# Monitoring_CB.net
KiCad netlist of a schematic drawn in Altium Designer
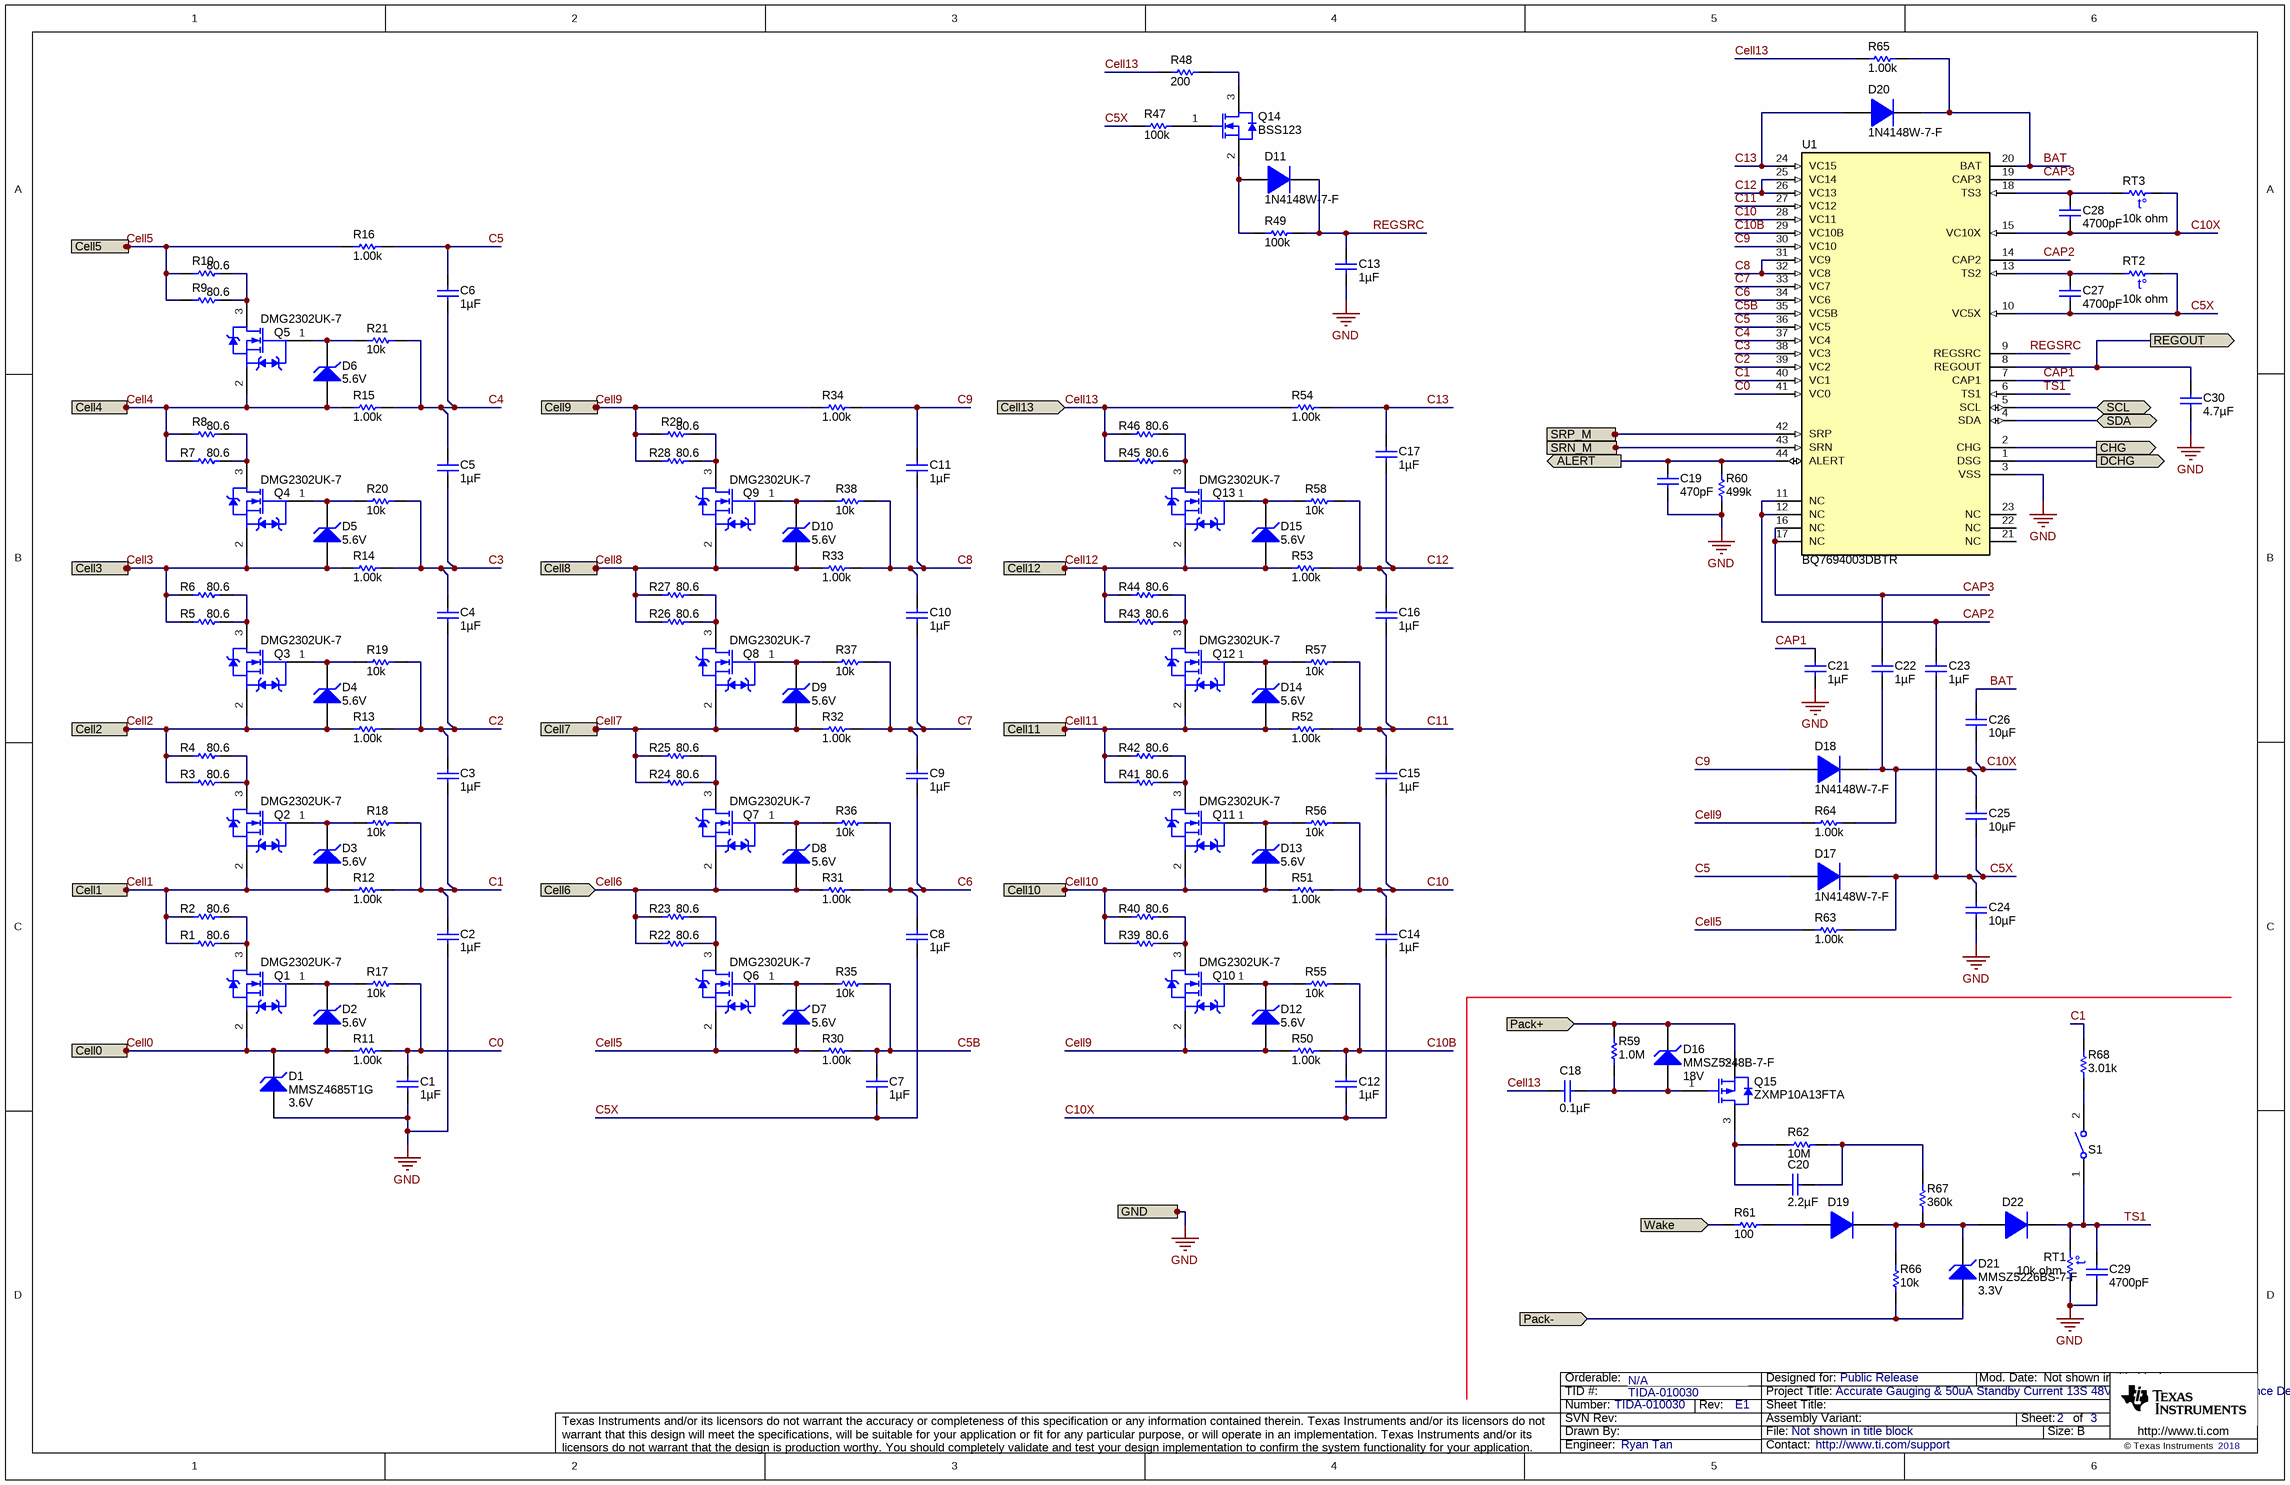
[diagram p0: Monitoring & CB.SchDoc]

(export (version "E")
  (design (tool "Eeschema 10.0.6"))
  (components
    (comp (ref "C1")
      (value "GRM188R71C105KE15D")
      (footprint "0603")
      (description "CAP, CERM, 1 µF, 16 V,+/- 10%, X7R, 0603")
      (fields
        (field (name "VALUEDISPLAYED") "1µF")
        (field (name "MANUFACTURER") "MuRata")
        (field (name "PUBLISHER") "Texas Instruments")
      )
      (libsource (lib "Capacitor_Ceramic") (part "GRM188R71C105KE15D"))
    )
    (comp (ref "C2")
      (value "GRM188R71C105KE15D")
      (footprint "0603S")
      (description "CAP, CERM, 1 µF, 16 V,+/- 10%, X7R, 0603")
      (fields
        (field (name "VALUEDISPLAYED") "1µF")
        (field (name "MANUFACTURER") "MuRata")
        (field (name "PUBLISHER") "Texas Instruments")
      )
      (libsource (lib "Capacitor_Ceramic") (part "GRM188R71C105KE15D"))
    )
    (comp (ref "C3")
      (value "GRM188R71C105KE15D")
      (footprint "0603")
      (description "CAP, CERM, 1 µF, 16 V,+/- 10%, X7R, 0603")
      (fields
        (field (name "VALUEDISPLAYED") "1µF")
        (field (name "MANUFACTURER") "MuRata")
        (field (name "PUBLISHER") "Texas Instruments")
      )
      (libsource (lib "Capacitor_Ceramic") (part "GRM188R71C105KE15D"))
    )
    (comp (ref "C4")
      (value "GRM188R71C105KE15D")
      (footprint "0603")
      (description "CAP, CERM, 1 µF, 16 V,+/- 10%, X7R, 0603")
      (fields
        (field (name "VALUEDISPLAYED") "1µF")
        (field (name "MANUFACTURER") "MuRata")
        (field (name "PUBLISHER") "Texas Instruments")
      )
      (libsource (lib "Capacitor_Ceramic") (part "GRM188R71C105KE15D"))
    )
    (comp (ref "C5")
      (value "GRM188R71C105KE15D")
      (footprint "0603")
      (description "CAP, CERM, 1 µF, 16 V,+/- 10%, X7R, 0603")
      (fields
        (field (name "VALUEDISPLAYED") "1µF")
        (field (name "MANUFACTURER") "MuRata")
        (field (name "PUBLISHER") "Texas Instruments")
      )
      (libsource (lib "Capacitor_Ceramic") (part "GRM188R71C105KE15D"))
    )
    (comp (ref "C6")
      (value "GRM188R71C105KE15D")
      (footprint "0603")
      (description "CAP, CERM, 1 µF, 16 V,+/- 10%, X7R, 0603")
      (fields
        (field (name "VALUEDISPLAYED") "1µF")
        (field (name "MANUFACTURER") "MuRata")
        (field (name "PUBLISHER") "Texas Instruments")
      )
      (libsource (lib "Capacitor_Ceramic") (part "GRM188R71C105KE15D"))
    )
    (comp (ref "C7")
      (value "GRM188R71C105KE15D")
      (footprint "0603S")
      (description "CAP, CERM, 1 µF, 16 V,+/- 10%, X7R, 0603")
      (fields
        (field (name "VALUEDISPLAYED") "1µF")
        (field (name "MANUFACTURER") "MuRata")
        (field (name "PUBLISHER") "Texas Instruments")
      )
      (libsource (lib "Capacitor_Ceramic") (part "GRM188R71C105KE15D"))
    )
    (comp (ref "C8")
      (value "GRM188R71C105KE15D")
      (footprint "0603S")
      (description "CAP, CERM, 1 µF, 16 V,+/- 10%, X7R, 0603")
      (fields
        (field (name "VALUEDISPLAYED") "1µF")
        (field (name "MANUFACTURER") "MuRata")
        (field (name "PUBLISHER") "Texas Instruments")
      )
      (libsource (lib "Capacitor_Ceramic") (part "GRM188R71C105KE15D"))
    )
    (comp (ref "C9")
      (value "GRM188R71C105KE15D")
      (footprint "0603")
      (description "CAP, CERM, 1 µF, 16 V,+/- 10%, X7R, 0603")
      (fields
        (field (name "VALUEDISPLAYED") "1µF")
        (field (name "MANUFACTURER") "MuRata")
        (field (name "PUBLISHER") "Texas Instruments")
      )
      (libsource (lib "Capacitor_Ceramic") (part "GRM188R71C105KE15D"))
    )
    (comp (ref "C10")
      (value "GRM188R71C105KE15D")
      (footprint "0603")
      (description "CAP, CERM, 1 µF, 16 V,+/- 10%, X7R, 0603")
      (fields
        (field (name "VALUEDISPLAYED") "1µF")
        (field (name "MANUFACTURER") "MuRata")
        (field (name "PUBLISHER") "Texas Instruments")
      )
      (libsource (lib "Capacitor_Ceramic") (part "GRM188R71C105KE15D"))
    )
    (comp (ref "C11")
      (value "GRM188R71C105KE15D")
      (footprint "0603")
      (description "CAP, CERM, 1 µF, 16 V,+/- 10%, X7R, 0603")
      (fields
        (field (name "VALUEDISPLAYED") "1µF")
        (field (name "MANUFACTURER") "MuRata")
        (field (name "PUBLISHER") "Texas Instruments")
      )
      (libsource (lib "Capacitor_Ceramic") (part "GRM188R71C105KE15D"))
    )
    (comp (ref "C12")
      (value "GRM188R71C105KE15D")
      (footprint "0603")
      (description "CAP, CERM, 1 µF, 16 V,+/- 10%, X7R, 0603")
      (fields
        (field (name "VALUEDISPLAYED") "1µF")
        (field (name "MANUFACTURER") "MuRata")
        (field (name "PUBLISHER") "Texas Instruments")
      )
      (libsource (lib "Capacitor_Ceramic") (part "GRM188R71C105KE15D"))
    )
    (comp (ref "C13")
      (value "C1608X7R1V105K080AC")
      (footprint "0603S")
      (description "CAP, CERM, 1 µF, 35 V,+/- 10%, X7R, 0603")
      (fields
        (field (name "VALUEDISPLAYED") "1µF")
        (field (name "MANUFACTURER") "TDK")
        (field (name "PUBLISHER") "Texas Instruments")
      )
      (libsource (lib "Capacitor_Ceramic") (part "C1608X7R1V105K080AC"))
    )
    (comp (ref "C14")
      (value "GRM188R71C105KE15D")
      (footprint "0603")
      (description "CAP, CERM, 1 µF, 16 V,+/- 10%, X7R, 0603")
      (fields
        (field (name "VALUEDISPLAYED") "1µF")
        (field (name "MANUFACTURER") "MuRata")
        (field (name "PUBLISHER") "Texas Instruments")
      )
      (libsource (lib "Capacitor_Ceramic") (part "GRM188R71C105KE15D"))
    )
    (comp (ref "C15")
      (value "GRM188R71C105KE15D")
      (footprint "0603")
      (description "CAP, CERM, 1 µF, 16 V,+/- 10%, X7R, 0603")
      (fields
        (field (name "VALUEDISPLAYED") "1µF")
        (field (name "MANUFACTURER") "MuRata")
        (field (name "PUBLISHER") "Texas Instruments")
      )
      (libsource (lib "Capacitor_Ceramic") (part "GRM188R71C105KE15D"))
    )
    (comp (ref "C16")
      (value "GRM188R71C105KE15D")
      (footprint "0603")
      (description "CAP, CERM, 1 µF, 16 V,+/- 10%, X7R, 0603")
      (fields
        (field (name "VALUEDISPLAYED") "1µF")
        (field (name "MANUFACTURER") "MuRata")
        (field (name "PUBLISHER") "Texas Instruments")
      )
      (libsource (lib "Capacitor_Ceramic") (part "GRM188R71C105KE15D"))
    )
    (comp (ref "C17")
      (value "GRM188R71C105KE15D")
      (footprint "0603")
      (description "CAP, CERM, 1 µF, 16 V,+/- 10%, X7R, 0603")
      (fields
        (field (name "VALUEDISPLAYED") "1µF")
        (field (name "MANUFACTURER") "MuRata")
        (field (name "PUBLISHER") "Texas Instruments")
      )
      (libsource (lib "Capacitor_Ceramic") (part "GRM188R71C105KE15D"))
    )
    (comp (ref "C18")
      (value "CGA4J2X7R2A104K125AA")
      (footprint "0805_HV")
      (description "CAP, CERM, 0.1 µF, 100 V,+/- 10%, X7R, AEC-Q200 Grade 1, 0805")
      (fields
        (field (name "VALUEDISPLAYED") "0.1µF")
        (field (name "MANUFACTURER") "TDK")
        (field (name "PUBLISHER") "Texas Instruments")
      )
      (libsource (lib "Capacitor_Ceramic") (part "CGA4J2X7R2A104K125AA"))
    )
    (comp (ref "C19")
      (value "GCM1885C1H471JA16D")
      (footprint "0603")
      (description "CAP, CERM, 470 pF, 50 V,+/- 5%, C0G/NP0, AEC-Q200 Grade 1, 0603")
      (fields
        (field (name "VALUEDISPLAYED") "470pF")
        (field (name "MANUFACTURER") "MuRata")
        (field (name "PUBLISHER") "Texas Instruments")
      )
      (libsource (lib "Capacitor_Ceramic") (part "GCM1885C1H471JA16D"))
    )
    (comp (ref "C20")
      (value "GRM32ER72A225KA35L")
      (footprint "1210_270")
      (description "CAP, CERM, 2.2 µF, 100 V,+/- 10%, X7R, 1210")
      (fields
        (field (name "VALUEDISPLAYED") "2.2µF")
        (field (name "MANUFACTURER") "MuRata")
        (field (name "PUBLISHER") "Texas Instruments")
      )
      (libsource (lib "Capacitor_Ceramic") (part "GRM32ER72A225KA35L"))
    )
    (comp (ref "C21")
      (value "GRM188R71C105KE15D")
      (footprint "0603S")
      (description "CAP, CERM, 1 µF, 16 V,+/- 10%, X7R, 0603")
      (fields
        (field (name "VALUEDISPLAYED") "1µF")
        (field (name "MANUFACTURER") "MuRata")
        (field (name "PUBLISHER") "Texas Instruments")
      )
      (libsource (lib "Capacitor_Ceramic") (part "GRM188R71C105KE15D"))
    )
    (comp (ref "C22")
      (value "GRM188R71C105KE15D")
      (footprint "0603S")
      (description "CAP, CERM, 1 µF, 16 V,+/- 10%, X7R, 0603")
      (fields
        (field (name "VALUEDISPLAYED") "1µF")
        (field (name "MANUFACTURER") "MuRata")
        (field (name "PUBLISHER") "Texas Instruments")
      )
      (libsource (lib "Capacitor_Ceramic") (part "GRM188R71C105KE15D"))
    )
    (comp (ref "C23")
      (value "GRM188R71C105KE15D")
      (footprint "0603S")
      (description "CAP, CERM, 1 µF, 16 V,+/- 10%, X7R, 0603")
      (fields
        (field (name "VALUEDISPLAYED") "1µF")
        (field (name "MANUFACTURER") "MuRata")
        (field (name "PUBLISHER") "Texas Instruments")
      )
      (libsource (lib "Capacitor_Ceramic") (part "GRM188R71C105KE15D"))
    )
    (comp (ref "C24")
      (value "C3225X5R1H106K250AB")
      (footprint "1210_280")
      (description "CAP, CERM, 10 µF, 50 V,+/- 10%, X5R, 1210")
      (fields
        (field (name "VALUEDISPLAYED") "10µF")
        (field (name "MANUFACTURER") "TDK")
        (field (name "PUBLISHER") "Texas Instruments")
      )
      (libsource (lib "Capacitor_Ceramic") (part "C3225X5R1H106K250AB"))
    )
    (comp (ref "C25")
      (value "C3225X5R1H106K250AB")
      (footprint "1210_280")
      (description "CAP, CERM, 10 µF, 50 V,+/- 10%, X5R, 1210")
      (fields
        (field (name "VALUEDISPLAYED") "10µF")
        (field (name "MANUFACTURER") "TDK")
        (field (name "PUBLISHER") "Texas Instruments")
      )
      (libsource (lib "Capacitor_Ceramic") (part "C3225X5R1H106K250AB"))
    )
    (comp (ref "C26")
      (value "C3225X5R1H106K250AB")
      (footprint "1210_280")
      (description "CAP, CERM, 10 µF, 50 V,+/- 10%, X5R, 1210")
      (fields
        (field (name "VALUEDISPLAYED") "10µF")
        (field (name "MANUFACTURER") "TDK")
        (field (name "PUBLISHER") "Texas Instruments")
      )
      (libsource (lib "Capacitor_Ceramic") (part "C3225X5R1H106K250AB"))
    )
    (comp (ref "C27")
      (value "GCM188R71H472KA37D")
      (footprint "0603S")
      (description "CAP, CERM, 4700 pF, 50 V,+/- 10%, X7R, AEC-Q200 Grade 1, 0603")
      (fields
        (field (name "VALUEDISPLAYED") "4700pF")
        (field (name "MANUFACTURER") "MuRata")
        (field (name "PUBLISHER") "Texas Instruments")
      )
      (libsource (lib "Capacitor_Ceramic") (part "GCM188R71H472KA37D"))
    )
    (comp (ref "C28")
      (value "GCM188R71H472KA37D")
      (footprint "0603")
      (description "CAP, CERM, 4700 pF, 50 V,+/- 10%, X7R, AEC-Q200 Grade 1, 0603")
      (fields
        (field (name "VALUEDISPLAYED") "4700pF")
        (field (name "MANUFACTURER") "MuRata")
        (field (name "PUBLISHER") "Texas Instruments")
      )
      (libsource (lib "Capacitor_Ceramic") (part "GCM188R71H472KA37D"))
    )
    (comp (ref "C29")
      (value "GCM188R71H472KA37D")
      (footprint "0603")
      (description "CAP, CERM, 4700 pF, 50 V,+/- 10%, X7R, AEC-Q200 Grade 1, 0603")
      (fields
        (field (name "VALUEDISPLAYED") "4700pF")
        (field (name "MANUFACTURER") "MuRata")
        (field (name "PUBLISHER") "Texas Instruments")
      )
      (libsource (lib "Capacitor_Ceramic") (part "GCM188R71H472KA37D"))
    )
    (comp (ref "C30")
      (value "GRM188R61C475KAAJ")
      (footprint "0603S")
      (description "CAP, CERM, 4.7 µF, 16 V,+/- 10%, X5R, 0603")
      (fields
        (field (name "VALUEDISPLAYED") "4.7µF")
        (field (name "MANUFACTURER") "MuRata")
        (field (name "PUBLISHER") "Texas Instruments")
      )
      (libsource (lib "Capacitor_Ceramic") (part "GRM188R61C475KAAJ"))
    )
    (comp (ref "D1")
      (value "MMSZ4685T1G")
      (footprint "SOD-123")
      (description "Diode, Zener, 3.6 V, 500 mW, SOD-123")
      (fields
        (field (name "ALTIUM_VALUE") "3.6V")
        (field (name "MANUFACTURER") "ON Semiconductor")
        (field (name "SYMBOLCREATOR") "a0412235")
        (field (name "PUBLISHER") "Texas Instruments")
      )
      (libsource (lib "ZenerDiodes") (part "MMSZ4685T1G"))
    )
    (comp (ref "D2")
      (value "5.6V")
      (footprint "SOD-523")
      (description "Diode, Zener, 5.6 V, 300 mW, SOD-523")
      (fields
        (field (name "PARTNUMBER") "BZT52C5V6T-7")
        (field (name "MANUFACTURER") "Diodes Inc.")
        (field (name "SYMBOLCREATOR") "a0412235")
        (field (name "PUBLISHER") "Texas Instruments")
      )
      (libsource (lib "ZenerDiodes") (part "BZT52C5V6T-7"))
    )
    (comp (ref "D3")
      (value "5.6V")
      (footprint "SOD-523")
      (description "Diode, Zener, 5.6 V, 300 mW, SOD-523")
      (fields
        (field (name "PARTNUMBER") "BZT52C5V6T-7")
        (field (name "MANUFACTURER") "Diodes Inc.")
        (field (name "SYMBOLCREATOR") "a0412235")
        (field (name "PUBLISHER") "Texas Instruments")
      )
      (libsource (lib "ZenerDiodes") (part "BZT52C5V6T-7"))
    )
    (comp (ref "D4")
      (value "5.6V")
      (footprint "SOD-523")
      (description "Diode, Zener, 5.6 V, 300 mW, SOD-523")
      (fields
        (field (name "PARTNUMBER") "BZT52C5V6T-7")
        (field (name "MANUFACTURER") "Diodes Inc.")
        (field (name "SYMBOLCREATOR") "a0412235")
        (field (name "PUBLISHER") "Texas Instruments")
      )
      (libsource (lib "ZenerDiodes") (part "BZT52C5V6T-7"))
    )
    (comp (ref "D5")
      (value "5.6V")
      (footprint "SOD-523")
      (description "Diode, Zener, 5.6 V, 300 mW, SOD-523")
      (fields
        (field (name "PARTNUMBER") "BZT52C5V6T-7")
        (field (name "MANUFACTURER") "Diodes Inc.")
        (field (name "SYMBOLCREATOR") "a0412235")
        (field (name "PUBLISHER") "Texas Instruments")
      )
      (libsource (lib "ZenerDiodes") (part "BZT52C5V6T-7"))
    )
    (comp (ref "D6")
      (value "5.6V")
      (footprint "SOD-523")
      (description "Diode, Zener, 5.6 V, 300 mW, SOD-523")
      (fields
        (field (name "PARTNUMBER") "BZT52C5V6T-7")
        (field (name "MANUFACTURER") "Diodes Inc.")
        (field (name "SYMBOLCREATOR") "a0412235")
        (field (name "PUBLISHER") "Texas Instruments")
      )
      (libsource (lib "ZenerDiodes") (part "BZT52C5V6T-7"))
    )
    (comp (ref "D7")
      (value "5.6V")
      (footprint "SOD-523")
      (description "Diode, Zener, 5.6 V, 300 mW, SOD-523")
      (fields
        (field (name "PARTNUMBER") "BZT52C5V6T-7")
        (field (name "MANUFACTURER") "Diodes Inc.")
        (field (name "SYMBOLCREATOR") "a0412235")
        (field (name "PUBLISHER") "Texas Instruments")
      )
      (libsource (lib "ZenerDiodes") (part "BZT52C5V6T-7"))
    )
    (comp (ref "D8")
      (value "5.6V")
      (footprint "SOD-523")
      (description "Diode, Zener, 5.6 V, 300 mW, SOD-523")
      (fields
        (field (name "PARTNUMBER") "BZT52C5V6T-7")
        (field (name "MANUFACTURER") "Diodes Inc.")
        (field (name "SYMBOLCREATOR") "a0412235")
        (field (name "PUBLISHER") "Texas Instruments")
      )
      (libsource (lib "ZenerDiodes") (part "BZT52C5V6T-7"))
    )
    (comp (ref "D9")
      (value "5.6V")
      (footprint "SOD-523")
      (description "Diode, Zener, 5.6 V, 300 mW, SOD-523")
      (fields
        (field (name "PARTNUMBER") "BZT52C5V6T-7")
        (field (name "MANUFACTURER") "Diodes Inc.")
        (field (name "SYMBOLCREATOR") "a0412235")
        (field (name "PUBLISHER") "Texas Instruments")
      )
      (libsource (lib "ZenerDiodes") (part "BZT52C5V6T-7"))
    )
    (comp (ref "D10")
      (value "5.6V")
      (footprint "SOD-523")
      (description "Diode, Zener, 5.6 V, 300 mW, SOD-523")
      (fields
        (field (name "PARTNUMBER") "BZT52C5V6T-7")
        (field (name "MANUFACTURER") "Diodes Inc.")
        (field (name "SYMBOLCREATOR") "a0412235")
        (field (name "PUBLISHER") "Texas Instruments")
      )
      (libsource (lib "ZenerDiodes") (part "BZT52C5V6T-7"))
    )
    (comp (ref "D11")
      (value "1N4148W-7-F")
      (footprint "SOD-123")
      (description "Diode, Ultrafast, 100 V, 0.15 A, SOD-123")
      (fields (field (name "MANUFACTURER") "Diodes Inc.") (field (name "PUBLISHER") "Texas Instruments"))
      (libsource (lib "Diode") (part "1N4148W-7-F"))
    )
    (comp (ref "D12")
      (value "5.6V")
      (footprint "SOD-523")
      (description "Diode, Zener, 5.6 V, 300 mW, SOD-523")
      (fields
        (field (name "PARTNUMBER") "BZT52C5V6T-7")
        (field (name "MANUFACTURER") "Diodes Inc.")
        (field (name "SYMBOLCREATOR") "a0412235")
        (field (name "PUBLISHER") "Texas Instruments")
      )
      (libsource (lib "ZenerDiodes") (part "BZT52C5V6T-7"))
    )
    (comp (ref "D13")
      (value "5.6V")
      (footprint "SOD-523")
      (description "Diode, Zener, 5.6 V, 300 mW, SOD-523")
      (fields
        (field (name "PARTNUMBER") "BZT52C5V6T-7")
        (field (name "MANUFACTURER") "Diodes Inc.")
        (field (name "SYMBOLCREATOR") "a0412235")
        (field (name "PUBLISHER") "Texas Instruments")
      )
      (libsource (lib "ZenerDiodes") (part "BZT52C5V6T-7"))
    )
    (comp (ref "D14")
      (value "5.6V")
      (footprint "SOD-523")
      (description "Diode, Zener, 5.6 V, 300 mW, SOD-523")
      (fields
        (field (name "PARTNUMBER") "BZT52C5V6T-7")
        (field (name "MANUFACTURER") "Diodes Inc.")
        (field (name "SYMBOLCREATOR") "a0412235")
        (field (name "PUBLISHER") "Texas Instruments")
      )
      (libsource (lib "ZenerDiodes") (part "BZT52C5V6T-7"))
    )
    (comp (ref "D15")
      (value "5.6V")
      (footprint "SOD-523")
      (description "Diode, Zener, 5.6 V, 300 mW, SOD-523")
      (fields
        (field (name "PARTNUMBER") "BZT52C5V6T-7")
        (field (name "MANUFACTURER") "Diodes Inc.")
        (field (name "SYMBOLCREATOR") "a0412235")
        (field (name "PUBLISHER") "Texas Instruments")
      )
      (libsource (lib "ZenerDiodes") (part "BZT52C5V6T-7"))
    )
    (comp (ref "D16")
      (value "MMSZ5248B-7-F")
      (footprint "SOD-123")
      (description "Diode, Zener, 18 V, 500 mW, SOD-123")
      (fields
        (field (name "ALTIUM_VALUE") "18V")
        (field (name "MANUFACTURER") "Diodes Inc.")
        (field (name "SYMBOLCREATOR") "a0412235")
        (field (name "PUBLISHER") "Texas Instruments")
      )
      (libsource (lib "ZenerDiodes") (part "MMSZ5248B-7-F"))
    )
    (comp (ref "D17")
      (value "1N4148W-7-F")
      (footprint "SOD-123")
      (description "Diode, Ultrafast, 100 V, 0.15 A, SOD-123")
      (fields (field (name "MANUFACTURER") "Diodes Inc.") (field (name "PUBLISHER") "Texas Instruments"))
      (libsource (lib "Diode") (part "1N4148W-7-F"))
    )
    (comp (ref "D18")
      (value "1N4148W-7-F")
      (footprint "SOD-123")
      (description "Diode, Ultrafast, 100 V, 0.15 A, SOD-123")
      (fields (field (name "MANUFACTURER") "Diodes Inc.") (field (name "PUBLISHER") "Texas Instruments"))
      (libsource (lib "Diode") (part "1N4148W-7-F"))
    )
    (comp (ref "D19")
      (value "SBR0220T5-7")
      (footprint "SOD-523")
      (description "Diode, Super Barrier Rectifier, 20 V, 0.2 A, SOD-523")
      (fields (field (name "MANUFACTURER") "Diodes Inc.") (field (name "PUBLISHER") "Texas Instruments"))
      (libsource (lib "Diode") (part "SBR0220T5-7"))
    )
    (comp (ref "D20")
      (value "1N4148W-7-F")
      (footprint "SOD-123")
      (description "Diode, Ultrafast, 100 V, 0.15 A, SOD-123")
      (fields (field (name "MANUFACTURER") "Diodes Inc.") (field (name "PUBLISHER") "Texas Instruments"))
      (libsource (lib "Diode") (part "1N4148W-7-F"))
    )
    (comp (ref "D21")
      (value "MMSZ5226BS-7-F")
      (footprint "SOD-323")
      (description "Diode, Zener, 3.3 V, 200 mW, SOD-323")
      (fields
        (field (name "ALTIUM_VALUE") "3.3V")
        (field (name "MANUFACTURER") "Diodes Inc.")
        (field (name "SYMBOLCREATOR") "a0412235")
        (field (name "PUBLISHER") "Texas Instruments")
      )
      (libsource (lib "ZenerDiodes") (part "MMSZ5226BS-7-F"))
    )
    (comp (ref "D22")
      (value "SBR0220T5-7")
      (footprint "SOD-523")
      (description "Diode, Super Barrier Rectifier, 20 V, 0.2 A, SOD-523")
      (fields (field (name "MANUFACTURER") "Diodes Inc.") (field (name "PUBLISHER") "Texas Instruments"))
      (libsource (lib "Diode") (part "SBR0220T5-7"))
    )
    (comp (ref "Q1")
      (value "DMG2302UK-7")
      (footprint "SOT-23")
      (description "MOSFET, N-CH, 20 V, 2.8 A, AEC-Q101, SOT-23")
      (fields
        (field (name "MANUFACTURER") "Diodes Inc.")
        (field (name "SYMBOLCREATOR") "x0208325")
        (field (name "PUBLISHER") "Texas Instruments")
      )
      (libsource (lib "FETs") (part "DMG2302UK-7"))
    )
    (comp (ref "Q2")
      (value "DMG2302UK-7")
      (footprint "SOT-23")
      (description "MOSFET, N-CH, 20 V, 2.8 A, AEC-Q101, SOT-23")
      (fields
        (field (name "MANUFACTURER") "Diodes Inc.")
        (field (name "SYMBOLCREATOR") "x0208325")
        (field (name "PUBLISHER") "Texas Instruments")
      )
      (libsource (lib "FETs") (part "DMG2302UK-7"))
    )
    (comp (ref "Q3")
      (value "DMG2302UK-7")
      (footprint "SOT-23")
      (description "MOSFET, N-CH, 20 V, 2.8 A, AEC-Q101, SOT-23")
      (fields
        (field (name "MANUFACTURER") "Diodes Inc.")
        (field (name "SYMBOLCREATOR") "x0208325")
        (field (name "PUBLISHER") "Texas Instruments")
      )
      (libsource (lib "FETs") (part "DMG2302UK-7"))
    )
    (comp (ref "Q4")
      (value "DMG2302UK-7")
      (footprint "SOT-23")
      (description "MOSFET, N-CH, 20 V, 2.8 A, AEC-Q101, SOT-23")
      (fields
        (field (name "MANUFACTURER") "Diodes Inc.")
        (field (name "SYMBOLCREATOR") "x0208325")
        (field (name "PUBLISHER") "Texas Instruments")
      )
      (libsource (lib "FETs") (part "DMG2302UK-7"))
    )
    (comp (ref "Q5")
      (value "DMG2302UK-7")
      (footprint "SOT-23")
      (description "MOSFET, N-CH, 20 V, 2.8 A, AEC-Q101, SOT-23")
      (fields
        (field (name "MANUFACTURER") "Diodes Inc.")
        (field (name "SYMBOLCREATOR") "x0208325")
        (field (name "PUBLISHER") "Texas Instruments")
      )
      (libsource (lib "FETs") (part "DMG2302UK-7"))
    )
    (comp (ref "Q6")
      (value "DMG2302UK-7")
      (footprint "SOT-23")
      (description "MOSFET, N-CH, 20 V, 2.8 A, AEC-Q101, SOT-23")
      (fields
        (field (name "MANUFACTURER") "Diodes Inc.")
        (field (name "SYMBOLCREATOR") "x0208325")
        (field (name "PUBLISHER") "Texas Instruments")
      )
      (libsource (lib "FETs") (part "DMG2302UK-7"))
    )
    (comp (ref "Q7")
      (value "DMG2302UK-7")
      (footprint "SOT-23")
      (description "MOSFET, N-CH, 20 V, 2.8 A, AEC-Q101, SOT-23")
      (fields
        (field (name "MANUFACTURER") "Diodes Inc.")
        (field (name "SYMBOLCREATOR") "x0208325")
        (field (name "PUBLISHER") "Texas Instruments")
      )
      (libsource (lib "FETs") (part "DMG2302UK-7"))
    )
    (comp (ref "Q8")
      (value "DMG2302UK-7")
      (footprint "SOT-23")
      (description "MOSFET, N-CH, 20 V, 2.8 A, AEC-Q101, SOT-23")
      (fields
        (field (name "MANUFACTURER") "Diodes Inc.")
        (field (name "SYMBOLCREATOR") "x0208325")
        (field (name "PUBLISHER") "Texas Instruments")
      )
      (libsource (lib "FETs") (part "DMG2302UK-7"))
    )
    (comp (ref "Q9")
      (value "DMG2302UK-7")
      (footprint "SOT-23")
      (description "MOSFET, N-CH, 20 V, 2.8 A, AEC-Q101, SOT-23")
      (fields
        (field (name "MANUFACTURER") "Diodes Inc.")
        (field (name "SYMBOLCREATOR") "x0208325")
        (field (name "PUBLISHER") "Texas Instruments")
      )
      (libsource (lib "FETs") (part "DMG2302UK-7"))
    )
    (comp (ref "Q10")
      (value "DMG2302UK-7")
      (footprint "SOT-23")
      (description "MOSFET, N-CH, 20 V, 2.8 A, AEC-Q101, SOT-23")
      (fields
        (field (name "MANUFACTURER") "Diodes Inc.")
        (field (name "SYMBOLCREATOR") "x0208325")
        (field (name "PUBLISHER") "Texas Instruments")
      )
      (libsource (lib "FETs") (part "DMG2302UK-7"))
    )
    (comp (ref "Q11")
      (value "DMG2302UK-7")
      (footprint "SOT-23")
      (description "MOSFET, N-CH, 20 V, 2.8 A, AEC-Q101, SOT-23")
      (fields
        (field (name "MANUFACTURER") "Diodes Inc.")
        (field (name "SYMBOLCREATOR") "x0208325")
        (field (name "PUBLISHER") "Texas Instruments")
      )
      (libsource (lib "FETs") (part "DMG2302UK-7"))
    )
    (comp (ref "Q12")
      (value "DMG2302UK-7")
      (footprint "SOT-23")
      (description "MOSFET, N-CH, 20 V, 2.8 A, AEC-Q101, SOT-23")
      (fields
        (field (name "MANUFACTURER") "Diodes Inc.")
        (field (name "SYMBOLCREATOR") "x0208325")
        (field (name "PUBLISHER") "Texas Instruments")
      )
      (libsource (lib "FETs") (part "DMG2302UK-7"))
    )
    (comp (ref "Q13")
      (value "DMG2302UK-7")
      (footprint "SOT-23")
      (description "MOSFET, N-CH, 20 V, 2.8 A, AEC-Q101, SOT-23")
      (fields
        (field (name "MANUFACTURER") "Diodes Inc.")
        (field (name "SYMBOLCREATOR") "x0208325")
        (field (name "PUBLISHER") "Texas Instruments")
      )
      (libsource (lib "FETs") (part "DMG2302UK-7"))
    )
    (comp (ref "Q14")
      (value "BSS123")
      (footprint "SOT-23")
      (description "MOSFET, N-CH, 100 V, 0.17 A, SOT-23")
      (fields
        (field (name "MANUFACTURER") "Fairchild Semiconductor")
        (field (name "PUBLISHER") "Texas Instruments")
      )
      (libsource (lib "FETs") (part "BSS123"))
    )
    (comp (ref "Q15")
      (value "ZXMP10A13FTA")
      (footprint "SOT-23")
      (description "MOSFET, P-CH, -100 V, -0.6 A, SOT-23")
      (fields (field (name "MANUFACTURER") "Diodes Inc.") (field (name "PUBLISHER") "Texas Instruments"))
      (libsource (lib "FETs") (part "ZXMP10A13FTA"))
    )
    (comp (ref "R1")
      (value "CRCW120680R6FKEA")
      (footprint "1206")
      (description "RES, 80.6, 1%, 0.25 W, 1206")
      (fields
        (field (name "VALUEDISPLAYED") "80.6")
        (field (name "MANUFACTURER") "Vishay-Dale")
        (field (name "PUBLISHER") "Texas Instruments")
      )
      (libsource (lib "Resistor_1206") (part "CRCW120680R6FKEA"))
    )
    (comp (ref "R2")
      (value "CRCW120680R6FKEA")
      (footprint "1206")
      (description "RES, 80.6, 1%, 0.25 W, 1206")
      (fields
        (field (name "VALUEDISPLAYED") "80.6")
        (field (name "MANUFACTURER") "Vishay-Dale")
        (field (name "PUBLISHER") "Texas Instruments")
      )
      (libsource (lib "Resistor_1206") (part "CRCW120680R6FKEA"))
    )
    (comp (ref "R3")
      (value "CRCW120680R6FKEA")
      (footprint "1206")
      (description "RES, 80.6, 1%, 0.25 W, 1206")
      (fields
        (field (name "VALUEDISPLAYED") "80.6")
        (field (name "MANUFACTURER") "Vishay-Dale")
        (field (name "PUBLISHER") "Texas Instruments")
      )
      (libsource (lib "Resistor_1206") (part "CRCW120680R6FKEA"))
    )
    (comp (ref "R4")
      (value "CRCW120680R6FKEA")
      (footprint "1206")
      (description "RES, 80.6, 1%, 0.25 W, 1206")
      (fields
        (field (name "VALUEDISPLAYED") "80.6")
        (field (name "MANUFACTURER") "Vishay-Dale")
        (field (name "PUBLISHER") "Texas Instruments")
      )
      (libsource (lib "Resistor_1206") (part "CRCW120680R6FKEA"))
    )
    (comp (ref "R5")
      (value "CRCW120680R6FKEA")
      (footprint "1206")
      (description "RES, 80.6, 1%, 0.25 W, 1206")
      (fields
        (field (name "VALUEDISPLAYED") "80.6")
        (field (name "MANUFACTURER") "Vishay-Dale")
        (field (name "PUBLISHER") "Texas Instruments")
      )
      (libsource (lib "Resistor_1206") (part "CRCW120680R6FKEA"))
    )
    (comp (ref "R6")
      (value "CRCW120680R6FKEA")
      (footprint "1206")
      (description "RES, 80.6, 1%, 0.25 W, 1206")
      (fields
        (field (name "VALUEDISPLAYED") "80.6")
        (field (name "MANUFACTURER") "Vishay-Dale")
        (field (name "PUBLISHER") "Texas Instruments")
      )
      (libsource (lib "Resistor_1206") (part "CRCW120680R6FKEA"))
    )
    (comp (ref "R7")
      (value "CRCW120680R6FKEA")
      (footprint "1206")
      (description "RES, 80.6, 1%, 0.25 W, 1206")
      (fields
        (field (name "VALUEDISPLAYED") "80.6")
        (field (name "MANUFACTURER") "Vishay-Dale")
        (field (name "PUBLISHER") "Texas Instruments")
      )
      (libsource (lib "Resistor_1206") (part "CRCW120680R6FKEA"))
    )
    (comp (ref "R8")
      (value "CRCW120680R6FKEA")
      (footprint "1206")
      (description "RES, 80.6, 1%, 0.25 W, 1206")
      (fields
        (field (name "VALUEDISPLAYED") "80.6")
        (field (name "MANUFACTURER") "Vishay-Dale")
        (field (name "PUBLISHER") "Texas Instruments")
      )
      (libsource (lib "Resistor_1206") (part "CRCW120680R6FKEA"))
    )
    (comp (ref "R9")
      (value "CRCW120680R6FKEA")
      (footprint "1206")
      (description "RES, 80.6, 1%, 0.25 W, 1206")
      (fields
        (field (name "VALUEDISPLAYED") "80.6")
        (field (name "MANUFACTURER") "Vishay-Dale")
        (field (name "PUBLISHER") "Texas Instruments")
      )
      (libsource (lib "Resistor_1206") (part "CRCW120680R6FKEA"))
    )
    (comp (ref "R10")
      (value "CRCW120680R6FKEA")
      (footprint "1206")
      (description "RES, 80.6, 1%, 0.25 W, 1206")
      (fields
        (field (name "VALUEDISPLAYED") "80.6")
        (field (name "MANUFACTURER") "Vishay-Dale")
        (field (name "PUBLISHER") "Texas Instruments")
      )
      (libsource (lib "Resistor_1206") (part "CRCW120680R6FKEA"))
    )
    (comp (ref "R11")
      (value "CRCW06031K00FKEA")
      (footprint "0603")
      (description "RES, 1.00 k, 1%, 0.1 W, 0603")
      (fields
        (field (name "VALUEDISPLAYED") "1.00k")
        (field (name "MANUFACTURER") "Vishay-Dale")
        (field (name "PUBLISHER") "Texas Instruments")
      )
      (libsource (lib "Resistor_0603") (part "CRCW06031K00FKEA"))
    )
    (comp (ref "R12")
      (value "CRCW06031K00FKEA")
      (footprint "0603")
      (description "RES, 1.00 k, 1%, 0.1 W, 0603")
      (fields
        (field (name "VALUEDISPLAYED") "1.00k")
        (field (name "MANUFACTURER") "Vishay-Dale")
        (field (name "PUBLISHER") "Texas Instruments")
      )
      (libsource (lib "Resistor_0603") (part "CRCW06031K00FKEA"))
    )
    (comp (ref "R13")
      (value "CRCW06031K00FKEA")
      (footprint "0603")
      (description "RES, 1.00 k, 1%, 0.1 W, 0603")
      (fields
        (field (name "VALUEDISPLAYED") "1.00k")
        (field (name "MANUFACTURER") "Vishay-Dale")
        (field (name "PUBLISHER") "Texas Instruments")
      )
      (libsource (lib "Resistor_0603") (part "CRCW06031K00FKEA"))
    )
    (comp (ref "R14")
      (value "CRCW06031K00FKEA")
      (footprint "0603")
      (description "RES, 1.00 k, 1%, 0.1 W, 0603")
      (fields
        (field (name "VALUEDISPLAYED") "1.00k")
        (field (name "MANUFACTURER") "Vishay-Dale")
        (field (name "PUBLISHER") "Texas Instruments")
      )
      (libsource (lib "Resistor_0603") (part "CRCW06031K00FKEA"))
    )
    (comp (ref "R15")
      (value "CRCW06031K00FKEA")
      (footprint "0603")
      (description "RES, 1.00 k, 1%, 0.1 W, 0603")
      (fields
        (field (name "VALUEDISPLAYED") "1.00k")
        (field (name "MANUFACTURER") "Vishay-Dale")
        (field (name "PUBLISHER") "Texas Instruments")
      )
      (libsource (lib "Resistor_0603") (part "CRCW06031K00FKEA"))
    )
    (comp (ref "R16")
      (value "CRCW06031K00FKEA")
      (footprint "0603")
      (description "RES, 1.00 k, 1%, 0.1 W, 0603")
      (fields
        (field (name "VALUEDISPLAYED") "1.00k")
        (field (name "MANUFACTURER") "Vishay-Dale")
        (field (name "PUBLISHER") "Texas Instruments")
      )
      (libsource (lib "Resistor_0603") (part "CRCW06031K00FKEA"))
    )
    (comp (ref "R17")
      (value "CRCW060310K0JNEA")
      (footprint "0603")
      (description "RES, 10 k, 5%, 0.1 W, 0603")
      (fields
        (field (name "VALUEDISPLAYED") "10k")
        (field (name "MANUFACTURER") "Vishay-Dale")
        (field (name "PUBLISHER") "Texas Instruments")
      )
      (libsource (lib "Resistor_0603") (part "CRCW060310K0JNEA"))
    )
    (comp (ref "R18")
      (value "CRCW060310K0JNEA")
      (footprint "0603")
      (description "RES, 10 k, 5%, 0.1 W, 0603")
      (fields
        (field (name "VALUEDISPLAYED") "10k")
        (field (name "MANUFACTURER") "Vishay-Dale")
        (field (name "PUBLISHER") "Texas Instruments")
      )
      (libsource (lib "Resistor_0603") (part "CRCW060310K0JNEA"))
    )
    (comp (ref "R19")
      (value "CRCW060310K0JNEA")
      (footprint "0603")
      (description "RES, 10 k, 5%, 0.1 W, 0603")
      (fields
        (field (name "VALUEDISPLAYED") "10k")
        (field (name "MANUFACTURER") "Vishay-Dale")
        (field (name "PUBLISHER") "Texas Instruments")
      )
      (libsource (lib "Resistor_0603") (part "CRCW060310K0JNEA"))
    )
    (comp (ref "R20")
      (value "CRCW060310K0JNEA")
      (footprint "0603")
      (description "RES, 10 k, 5%, 0.1 W, 0603")
      (fields
        (field (name "VALUEDISPLAYED") "10k")
        (field (name "MANUFACTURER") "Vishay-Dale")
        (field (name "PUBLISHER") "Texas Instruments")
      )
      (libsource (lib "Resistor_0603") (part "CRCW060310K0JNEA"))
    )
    (comp (ref "R21")
      (value "CRCW060310K0JNEA")
      (footprint "0603")
      (description "RES, 10 k, 5%, 0.1 W, 0603")
      (fields
        (field (name "VALUEDISPLAYED") "10k")
        (field (name "MANUFACTURER") "Vishay-Dale")
        (field (name "PUBLISHER") "Texas Instruments")
      )
      (libsource (lib "Resistor_0603") (part "CRCW060310K0JNEA"))
    )
    (comp (ref "R22")
      (value "CRCW120680R6FKEA")
      (footprint "1206")
      (description "RES, 80.6, 1%, 0.25 W, 1206")
      (fields
        (field (name "VALUEDISPLAYED") "80.6")
        (field (name "MANUFACTURER") "Vishay-Dale")
        (field (name "PUBLISHER") "Texas Instruments")
      )
      (libsource (lib "Resistor_1206") (part "CRCW120680R6FKEA"))
    )
    (comp (ref "R23")
      (value "CRCW120680R6FKEA")
      (footprint "1206")
      (description "RES, 80.6, 1%, 0.25 W, 1206")
      (fields
        (field (name "VALUEDISPLAYED") "80.6")
        (field (name "MANUFACTURER") "Vishay-Dale")
        (field (name "PUBLISHER") "Texas Instruments")
      )
      (libsource (lib "Resistor_1206") (part "CRCW120680R6FKEA"))
    )
    (comp (ref "R24")
      (value "CRCW120680R6FKEA")
      (footprint "1206")
      (description "RES, 80.6, 1%, 0.25 W, 1206")
      (fields
        (field (name "VALUEDISPLAYED") "80.6")
        (field (name "MANUFACTURER") "Vishay-Dale")
        (field (name "PUBLISHER") "Texas Instruments")
      )
      (libsource (lib "Resistor_1206") (part "CRCW120680R6FKEA"))
    )
    (comp (ref "R25")
      (value "CRCW120680R6FKEA")
      (footprint "1206")
      (description "RES, 80.6, 1%, 0.25 W, 1206")
      (fields
        (field (name "VALUEDISPLAYED") "80.6")
        (field (name "MANUFACTURER") "Vishay-Dale")
        (field (name "PUBLISHER") "Texas Instruments")
      )
      (libsource (lib "Resistor_1206") (part "CRCW120680R6FKEA"))
    )
    (comp (ref "R26")
      (value "CRCW120680R6FKEA")
      (footprint "1206")
      (description "RES, 80.6, 1%, 0.25 W, 1206")
      (fields
        (field (name "VALUEDISPLAYED") "80.6")
        (field (name "MANUFACTURER") "Vishay-Dale")
        (field (name "PUBLISHER") "Texas Instruments")
      )
      (libsource (lib "Resistor_1206") (part "CRCW120680R6FKEA"))
    )
    (comp (ref "R27")
      (value "CRCW120680R6FKEA")
      (footprint "1206")
      (description "RES, 80.6, 1%, 0.25 W, 1206")
      (fields
        (field (name "VALUEDISPLAYED") "80.6")
        (field (name "MANUFACTURER") "Vishay-Dale")
        (field (name "PUBLISHER") "Texas Instruments")
      )
      (libsource (lib "Resistor_1206") (part "CRCW120680R6FKEA"))
    )
    (comp (ref "R28")
      (value "CRCW120680R6FKEA")
      (footprint "1206")
      (description "RES, 80.6, 1%, 0.25 W, 1206")
      (fields
        (field (name "VALUEDISPLAYED") "80.6")
        (field (name "MANUFACTURER") "Vishay-Dale")
        (field (name "PUBLISHER") "Texas Instruments")
      )
      (libsource (lib "Resistor_1206") (part "CRCW120680R6FKEA"))
    )
    (comp (ref "R29")
      (value "CRCW120680R6FKEA")
      (footprint "1206")
      (description "RES, 80.6, 1%, 0.25 W, 1206")
      (fields
        (field (name "VALUEDISPLAYED") "80.6")
        (field (name "MANUFACTURER") "Vishay-Dale")
        (field (name "PUBLISHER") "Texas Instruments")
      )
      (libsource (lib "Resistor_1206") (part "CRCW120680R6FKEA"))
    )
    (comp (ref "R30")
      (value "CRCW06031K00FKEA")
      (footprint "0603")
      (description "RES, 1.00 k, 1%, 0.1 W, 0603")
      (fields
        (field (name "VALUEDISPLAYED") "1.00k")
        (field (name "MANUFACTURER") "Vishay-Dale")
        (field (name "PUBLISHER") "Texas Instruments")
      )
      (libsource (lib "Resistor_0603") (part "CRCW06031K00FKEA"))
    )
    (comp (ref "R31")
      (value "CRCW06031K00FKEA")
      (footprint "0603")
      (description "RES, 1.00 k, 1%, 0.1 W, 0603")
      (fields
        (field (name "VALUEDISPLAYED") "1.00k")
        (field (name "MANUFACTURER") "Vishay-Dale")
        (field (name "PUBLISHER") "Texas Instruments")
      )
      (libsource (lib "Resistor_0603") (part "CRCW06031K00FKEA"))
    )
    (comp (ref "R32")
      (value "CRCW06031K00FKEA")
      (footprint "0603")
      (description "RES, 1.00 k, 1%, 0.1 W, 0603")
      (fields
        (field (name "VALUEDISPLAYED") "1.00k")
        (field (name "MANUFACTURER") "Vishay-Dale")
        (field (name "PUBLISHER") "Texas Instruments")
      )
      (libsource (lib "Resistor_0603") (part "CRCW06031K00FKEA"))
    )
    (comp (ref "R33")
      (value "CRCW06031K00FKEA")
      (footprint "0603")
      (description "RES, 1.00 k, 1%, 0.1 W, 0603")
      (fields
        (field (name "VALUEDISPLAYED") "1.00k")
        (field (name "MANUFACTURER") "Vishay-Dale")
        (field (name "PUBLISHER") "Texas Instruments")
      )
      (libsource (lib "Resistor_0603") (part "CRCW06031K00FKEA"))
    )
    (comp (ref "R34")
      (value "CRCW06031K00FKEA")
      (footprint "0603")
      (description "RES, 1.00 k, 1%, 0.1 W, 0603")
      (fields
        (field (name "VALUEDISPLAYED") "1.00k")
        (field (name "MANUFACTURER") "Vishay-Dale")
        (field (name "PUBLISHER") "Texas Instruments")
      )
      (libsource (lib "Resistor_0603") (part "CRCW06031K00FKEA"))
    )
    (comp (ref "R35")
      (value "CRCW060310K0JNEA")
      (footprint "0603")
      (description "RES, 10 k, 5%, 0.1 W, 0603")
      (fields
        (field (name "VALUEDISPLAYED") "10k")
        (field (name "MANUFACTURER") "Vishay-Dale")
        (field (name "PUBLISHER") "Texas Instruments")
      )
      (libsource (lib "Resistor_0603") (part "CRCW060310K0JNEA"))
    )
    (comp (ref "R36")
      (value "CRCW060310K0JNEA")
      (footprint "0603")
      (description "RES, 10 k, 5%, 0.1 W, 0603")
      (fields
        (field (name "VALUEDISPLAYED") "10k")
        (field (name "MANUFACTURER") "Vishay-Dale")
        (field (name "PUBLISHER") "Texas Instruments")
      )
      (libsource (lib "Resistor_0603") (part "CRCW060310K0JNEA"))
    )
    (comp (ref "R37")
      (value "CRCW060310K0JNEA")
      (footprint "0603")
      (description "RES, 10 k, 5%, 0.1 W, 0603")
      (fields
        (field (name "VALUEDISPLAYED") "10k")
        (field (name "MANUFACTURER") "Vishay-Dale")
        (field (name "PUBLISHER") "Texas Instruments")
      )
      (libsource (lib "Resistor_0603") (part "CRCW060310K0JNEA"))
    )
    (comp (ref "R38")
      (value "CRCW060310K0JNEA")
      (footprint "0603")
      (description "RES, 10 k, 5%, 0.1 W, 0603")
      (fields
        (field (name "VALUEDISPLAYED") "10k")
        (field (name "MANUFACTURER") "Vishay-Dale")
        (field (name "PUBLISHER") "Texas Instruments")
      )
      (libsource (lib "Resistor_0603") (part "CRCW060310K0JNEA"))
    )
    (comp (ref "R39")
      (value "CRCW120680R6FKEA")
      (footprint "1206")
      (description "RES, 80.6, 1%, 0.25 W, 1206")
      (fields
        (field (name "VALUEDISPLAYED") "80.6")
        (field (name "MANUFACTURER") "Vishay-Dale")
        (field (name "PUBLISHER") "Texas Instruments")
      )
      (libsource (lib "Resistor_1206") (part "CRCW120680R6FKEA"))
    )
    (comp (ref "R40")
      (value "CRCW120680R6FKEA")
      (footprint "1206")
      (description "RES, 80.6, 1%, 0.25 W, 1206")
      (fields
        (field (name "VALUEDISPLAYED") "80.6")
        (field (name "MANUFACTURER") "Vishay-Dale")
        (field (name "PUBLISHER") "Texas Instruments")
      )
      (libsource (lib "Resistor_1206") (part "CRCW120680R6FKEA"))
    )
    (comp (ref "R41")
      (value "CRCW120680R6FKEA")
      (footprint "1206")
      (description "RES, 80.6, 1%, 0.25 W, 1206")
      (fields
        (field (name "VALUEDISPLAYED") "80.6")
        (field (name "MANUFACTURER") "Vishay-Dale")
        (field (name "PUBLISHER") "Texas Instruments")
      )
      (libsource (lib "Resistor_1206") (part "CRCW120680R6FKEA"))
    )
    (comp (ref "R42")
      (value "CRCW120680R6FKEA")
      (footprint "1206")
      (description "RES, 80.6, 1%, 0.25 W, 1206")
      (fields
        (field (name "VALUEDISPLAYED") "80.6")
        (field (name "MANUFACTURER") "Vishay-Dale")
        (field (name "PUBLISHER") "Texas Instruments")
      )
      (libsource (lib "Resistor_1206") (part "CRCW120680R6FKEA"))
    )
    (comp (ref "R43")
      (value "CRCW120680R6FKEA")
      (footprint "1206")
      (description "RES, 80.6, 1%, 0.25 W, 1206")
      (fields
        (field (name "VALUEDISPLAYED") "80.6")
        (field (name "MANUFACTURER") "Vishay-Dale")
        (field (name "PUBLISHER") "Texas Instruments")
      )
      (libsource (lib "Resistor_1206") (part "CRCW120680R6FKEA"))
    )
    (comp (ref "R44")
      (value "CRCW120680R6FKEA")
      (footprint "1206")
      (description "RES, 80.6, 1%, 0.25 W, 1206")
      (fields
        (field (name "VALUEDISPLAYED") "80.6")
        (field (name "MANUFACTURER") "Vishay-Dale")
        (field (name "PUBLISHER") "Texas Instruments")
      )
      (libsource (lib "Resistor_1206") (part "CRCW120680R6FKEA"))
    )
    (comp (ref "R45")
      (value "CRCW120680R6FKEA")
      (footprint "1206")
      (description "RES, 80.6, 1%, 0.25 W, 1206")
      (fields
        (field (name "VALUEDISPLAYED") "80.6")
        (field (name "MANUFACTURER") "Vishay-Dale")
        (field (name "PUBLISHER") "Texas Instruments")
      )
      (libsource (lib "Resistor_1206") (part "CRCW120680R6FKEA"))
    )
    (comp (ref "R46")
      (value "CRCW120680R6FKEA")
      (footprint "1206")
      (description "RES, 80.6, 1%, 0.25 W, 1206")
      (fields
        (field (name "VALUEDISPLAYED") "80.6")
        (field (name "MANUFACTURER") "Vishay-Dale")
        (field (name "PUBLISHER") "Texas Instruments")
      )
      (libsource (lib "Resistor_1206") (part "CRCW120680R6FKEA"))
    )
    (comp (ref "R47")
      (value "CRCW0603100KFKEA")
      (footprint "0603")
      (description "RES, 100 k, 1%, 0.1 W, 0603")
      (fields
        (field (name "VALUEDISPLAYED") "100k")
        (field (name "MANUFACTURER") "Vishay-Dale")
        (field (name "PUBLISHER") "Texas Instruments")
      )
      (libsource (lib "Resistor_0603") (part "CRCW0603100KFKEA"))
    )
    (comp (ref "R48")
      (value "CRCW0603200RFKEA")
      (footprint "0603")
      (description "RES, 200, 1%, 0.1 W, 0603")
      (fields
        (field (name "VALUEDISPLAYED") "200")
        (field (name "MANUFACTURER") "Vishay-Dale")
        (field (name "PUBLISHER") "Texas Instruments")
      )
      (libsource (lib "Resistor_0603") (part "CRCW0603200RFKEA"))
    )
    (comp (ref "R49")
      (value "CRCW0603100KFKEA")
      (footprint "0603")
      (description "RES, 100 k, 1%, 0.1 W, 0603")
      (fields
        (field (name "VALUEDISPLAYED") "100k")
        (field (name "MANUFACTURER") "Vishay-Dale")
        (field (name "PUBLISHER") "Texas Instruments")
      )
      (libsource (lib "Resistor_0603") (part "CRCW0603100KFKEA"))
    )
    (comp (ref "R50")
      (value "CRCW06031K00FKEA")
      (footprint "0603")
      (description "RES, 1.00 k, 1%, 0.1 W, 0603")
      (fields
        (field (name "VALUEDISPLAYED") "1.00k")
        (field (name "MANUFACTURER") "Vishay-Dale")
        (field (name "PUBLISHER") "Texas Instruments")
      )
      (libsource (lib "Resistor_0603") (part "CRCW06031K00FKEA"))
    )
    (comp (ref "R51")
      (value "CRCW06031K00FKEA")
      (footprint "0603")
      (description "RES, 1.00 k, 1%, 0.1 W, 0603")
      (fields
        (field (name "VALUEDISPLAYED") "1.00k")
        (field (name "MANUFACTURER") "Vishay-Dale")
        (field (name "PUBLISHER") "Texas Instruments")
      )
      (libsource (lib "Resistor_0603") (part "CRCW06031K00FKEA"))
    )
    (comp (ref "R52")
      (value "CRCW06031K00FKEA")
      (footprint "0603")
      (description "RES, 1.00 k, 1%, 0.1 W, 0603")
      (fields
        (field (name "VALUEDISPLAYED") "1.00k")
        (field (name "MANUFACTURER") "Vishay-Dale")
        (field (name "PUBLISHER") "Texas Instruments")
      )
      (libsource (lib "Resistor_0603") (part "CRCW06031K00FKEA"))
    )
    (comp (ref "R53")
      (value "CRCW06031K00FKEA")
      (footprint "0603")
      (description "RES, 1.00 k, 1%, 0.1 W, 0603")
      (fields
        (field (name "VALUEDISPLAYED") "1.00k")
        (field (name "MANUFACTURER") "Vishay-Dale")
        (field (name "PUBLISHER") "Texas Instruments")
      )
      (libsource (lib "Resistor_0603") (part "CRCW06031K00FKEA"))
    )
    (comp (ref "R54")
      (value "CRCW06031K00FKEA")
      (footprint "0603")
      (description "RES, 1.00 k, 1%, 0.1 W, 0603")
      (fields
        (field (name "VALUEDISPLAYED") "1.00k")
        (field (name "MANUFACTURER") "Vishay-Dale")
        (field (name "PUBLISHER") "Texas Instruments")
      )
      (libsource (lib "Resistor_0603") (part "CRCW06031K00FKEA"))
    )
    (comp (ref "R55")
      (value "CRCW060310K0JNEA")
      (footprint "0603")
      (description "RES, 10 k, 5%, 0.1 W, 0603")
      (fields
        (field (name "VALUEDISPLAYED") "10k")
        (field (name "MANUFACTURER") "Vishay-Dale")
        (field (name "PUBLISHER") "Texas Instruments")
      )
      (libsource (lib "Resistor_0603") (part "CRCW060310K0JNEA"))
    )
    (comp (ref "R56")
      (value "CRCW060310K0JNEA")
      (footprint "0603")
      (description "RES, 10 k, 5%, 0.1 W, 0603")
      (fields
        (field (name "VALUEDISPLAYED") "10k")
        (field (name "MANUFACTURER") "Vishay-Dale")
        (field (name "PUBLISHER") "Texas Instruments")
      )
      (libsource (lib "Resistor_0603") (part "CRCW060310K0JNEA"))
    )
    (comp (ref "R57")
      (value "CRCW060310K0JNEA")
      (footprint "0603")
      (description "RES, 10 k, 5%, 0.1 W, 0603")
      (fields
        (field (name "VALUEDISPLAYED") "10k")
        (field (name "MANUFACTURER") "Vishay-Dale")
        (field (name "PUBLISHER") "Texas Instruments")
      )
      (libsource (lib "Resistor_0603") (part "CRCW060310K0JNEA"))
    )
    (comp (ref "R58")
      (value "CRCW060310K0JNEA")
      (footprint "0603")
      (description "RES, 10 k, 5%, 0.1 W, 0603")
      (fields
        (field (name "VALUEDISPLAYED") "10k")
        (field (name "MANUFACTURER") "Vishay-Dale")
        (field (name "PUBLISHER") "Texas Instruments")
      )
      (libsource (lib "Resistor_0603") (part "CRCW060310K0JNEA"))
    )
    (comp (ref "R59")
      (value "CRCW06031M00JNEA")
      (footprint "0603")
      (description "RES, 1.0 M, 5%, 0.1 W, 0603")
      (fields
        (field (name "VALUEDISPLAYED") "1.0M")
        (field (name "MANUFACTURER") "Vishay-Dale")
        (field (name "PUBLISHER") "Texas Instruments")
      )
      (libsource (lib "Resistor_0603") (part "CRCW06031M00JNEA"))
    )
    (comp (ref "R60")
      (value "CRCW0603499KFKEA")
      (footprint "0603")
      (description "RES, 499 k, 1%, 0.1 W, 0603")
      (fields
        (field (name "VALUEDISPLAYED") "499k")
        (field (name "MANUFACTURER") "Vishay-Dale")
        (field (name "PUBLISHER") "Texas Instruments")
      )
      (libsource (lib "Resistor_0603") (part "CRCW0603499KFKEA"))
    )
    (comp (ref "R61")
      (value "CRCW0603100RFKEA")
      (footprint "0603")
      (description "RES, 100, 1%, 0.1 W, 0603")
      (fields
        (field (name "VALUEDISPLAYED") "100")
        (field (name "MANUFACTURER") "Vishay-Dale")
        (field (name "PUBLISHER") "Texas Instruments")
      )
      (libsource (lib "Resistor_0603") (part "CRCW0603100RFKEA"))
    )
    (comp (ref "R62")
      (value "CRCW060310M0JNEA")
      (footprint "0603")
      (description "RES, 10 M, 5%, 0.1 W, 0603")
      (fields
        (field (name "VALUEDISPLAYED") "10M")
        (field (name "MANUFACTURER") "Vishay-Dale")
        (field (name "PUBLISHER") "Texas Instruments")
      )
      (libsource (lib "Resistor_0603") (part "CRCW060310M0JNEA"))
    )
    (comp (ref "R63")
      (value "CRCW06031K00FKEA")
      (footprint "0603")
      (description "RES, 1.00 k, 1%, 0.1 W, 0603")
      (fields
        (field (name "VALUEDISPLAYED") "1.00k")
        (field (name "MANUFACTURER") "Vishay-Dale")
        (field (name "PUBLISHER") "Texas Instruments")
      )
      (libsource (lib "Resistor_0603") (part "CRCW06031K00FKEA"))
    )
    (comp (ref "R64")
      (value "CRCW06031K00FKEA")
      (footprint "0603")
      (description "RES, 1.00 k, 1%, 0.1 W, 0603")
      (fields
        (field (name "VALUEDISPLAYED") "1.00k")
        (field (name "MANUFACTURER") "Vishay-Dale")
        (field (name "PUBLISHER") "Texas Instruments")
      )
      (libsource (lib "Resistor_0603") (part "CRCW06031K00FKEA"))
    )
    (comp (ref "R65")
      (value "CRCW06031K00FKEA")
      (footprint "0603")
      (description "RES, 1.00 k, 1%, 0.1 W, 0603")
      (fields
        (field (name "VALUEDISPLAYED") "1.00k")
        (field (name "MANUFACTURER") "Vishay-Dale")
        (field (name "PUBLISHER") "Texas Instruments")
      )
      (libsource (lib "Resistor_0603") (part "CRCW06031K00FKEA"))
    )
    (comp (ref "R66")
      (value "CRCW060310K0JNEA")
      (footprint "0603")
      (description "RES, 10 k, 5%, 0.1 W, 0603")
      (fields
        (field (name "VALUEDISPLAYED") "10k")
        (field (name "MANUFACTURER") "Vishay-Dale")
        (field (name "PUBLISHER") "Texas Instruments")
      )
      (libsource (lib "Resistor_0603") (part "CRCW060310K0JNEA"))
    )
    (comp (ref "R67")
      (value "ERJ-3EKF3603V")
      (footprint "0603")
      (description "RES, 360 k, 1%, 0.1 W, AEC-Q200 Grade 0, 0603")
      (fields
        (field (name "VALUEDISPLAYED") "360k")
        (field (name "MANUFACTURER") "Panasonic")
        (field (name "PUBLISHER") "Texas Instruments")
      )
      (libsource (lib "Resistor_0603") (part "ERJ-3EKF3603V"))
    )
    (comp (ref "R68")
      (value "CRCW06033K01FKEA")
      (footprint "0603S")
      (description "RES, 3.01 k, 1%, 0.1 W, 0603")
      (fields
        (field (name "VALUEDISPLAYED") "3.01k")
        (field (name "MANUFACTURER") "Vishay-Dale")
        (field (name "PUBLISHER") "Texas Instruments")
      )
      (libsource (lib "Resistor_0603") (part "CRCW06033K01FKEA"))
    )
    (comp (ref "RT1")
      (value "10k ohm")
      (footprint "NTCALUG03")
      (description "Thermistor NTC, 10k ohm, 2%, NTC Thermistor, Mini Lug Sensor, Pitch 1.5mm")
      (fields
        (field (name "PARTNUMBER") "NTCALUG03A103G")
        (field (name "MANUFACTURER") "Vishay-Bccomponents")
        (field (name "PUBLISHER") "Texas Instruments")
      )
      (libsource (lib "ThermistorNTC") (part "NTCALUG03A103G"))
    )
    (comp (ref "RT2")
      (value "10k ohm")
      (footprint "NTCALUG03")
      (description "Thermistor NTC, 10k ohm, 2%, NTC Thermistor, Mini Lug Sensor, Pitch 1.5mm")
      (fields
        (field (name "PARTNUMBER") "NTCALUG03A103G")
        (field (name "MANUFACTURER") "Vishay-Bccomponents")
        (field (name "PUBLISHER") "Texas Instruments")
      )
      (libsource (lib "ThermistorNTC") (part "NTCALUG03A103G"))
    )
    (comp (ref "RT3")
      (value "10k ohm")
      (footprint "NTCALUG03")
      (description "Thermistor NTC, 10k ohm, 2%, NTC Thermistor, Mini Lug Sensor, Pitch 1.5mm")
      (fields
        (field (name "PARTNUMBER") "NTCALUG03A103G")
        (field (name "MANUFACTURER") "Vishay-Bccomponents")
        (field (name "PUBLISHER") "Texas Instruments")
      )
      (libsource (lib "ThermistorNTC") (part "NTCALUG03A103G"))
    )
    (comp (ref "S1")
      (value "RS-032G05A3-SM RT")
      (footprint "SW_RS-032G05A3-SM")
      (description "Switch, Tactile, SPST-NO, 0.05A, 12V, SMD")
      (fields
        (field (name "MANUFACTURER") "C&K Components")
        (field (name "SYMBOLCREATOR") "a0799628")
        (field (name "PUBLISHER") "Texas Instruments")
      )
      (libsource (lib "Switches") (part "RS-032G05A3-SM RT"))
    )
    (comp (ref "U1")
      (value "BQ7694003DBTR")
      (footprint "DBT0044A_N")
      (description "9 to 15-Series Cell Li-Ion and Li-Phosphate Battery Monitor (bq76940 Family), DBT0044A (TSSOP-44)")
      (fields
        (field (name "ALTERNATE PARTNUMBER") "BQ7694003DBT")
        (field (name "MANUFACTURER") "Texas Instruments")
        (field (name "PARTNUMBER") "BQ7694003DBTR")
        (field (name "PUBLISHER") "Texas Instruments")
      )
      (libsource (lib "Altium Vault - TI") (part "CMP-0065910-1"))
    )
  )
  (nets
    (net (code "1") (name "/ALERT") (class "Default")
      (node (ref "C19") (pin "1") (pinfunction "1_1") (pintype "passive"))
      (node (ref "R60") (pin "2") (pinfunction "2_2") (pintype "passive"))
      (node (ref "U1") (pin "44") (pinfunction "ALERT_44") (pintype "bidirectional"))
    )
    (net (code "2") (name "/BAT") (class "Default")
      (node (ref "C26") (pin "2") (pinfunction "2_2") (pintype "passive"))
      (node (ref "D20") (pin "1") (pinfunction "K_1") (pintype "passive"))
      (node (ref "R65") (pin "2") (pinfunction "2_2") (pintype "passive"))
      (node (ref "U1") (pin "20") (pinfunction "BAT_20") (pintype "power_in"))
    )
    (net (code "3") (name "/C0") (class "Default")
      (node (ref "C1") (pin "1") (pinfunction "1_1") (pintype "passive"))
      (node (ref "R11") (pin "2") (pinfunction "2_2") (pintype "passive"))
      (node (ref "R17") (pin "2") (pinfunction "2_2") (pintype "passive"))
      (node (ref "U1") (pin "41") (pinfunction "VC0_41") (pintype "input"))
    )
    (net (code "4") (name "/C1") (class "Default")
      (node (ref "C2") (pin "1") (pinfunction "1_1") (pintype "passive"))
      (node (ref "C3") (pin "2") (pinfunction "2_2") (pintype "passive"))
      (node (ref "R12") (pin "2") (pinfunction "2_2") (pintype "passive"))
      (node (ref "R18") (pin "2") (pinfunction "2_2") (pintype "passive"))
      (node (ref "R68") (pin "2") (pinfunction "2_2") (pintype "passive"))
      (node (ref "U1") (pin "40") (pinfunction "VC1_40") (pintype "input"))
    )
    (net (code "5") (name "/C2") (class "Default")
      (node (ref "C3") (pin "1") (pinfunction "1_1") (pintype "passive"))
      (node (ref "C4") (pin "2") (pinfunction "2_2") (pintype "passive"))
      (node (ref "R13") (pin "2") (pinfunction "2_2") (pintype "passive"))
      (node (ref "R19") (pin "2") (pinfunction "2_2") (pintype "passive"))
      (node (ref "U1") (pin "39") (pinfunction "VC2_39") (pintype "input"))
    )
    (net (code "6") (name "/C3") (class "Default")
      (node (ref "C4") (pin "1") (pinfunction "1_1") (pintype "passive"))
      (node (ref "C5") (pin "2") (pinfunction "2_2") (pintype "passive"))
      (node (ref "R14") (pin "2") (pinfunction "2_2") (pintype "passive"))
      (node (ref "R20") (pin "2") (pinfunction "2_2") (pintype "passive"))
      (node (ref "U1") (pin "38") (pinfunction "VC3_38") (pintype "input"))
    )
    (net (code "7") (name "/C4") (class "Default")
      (node (ref "C5") (pin "1") (pinfunction "1_1") (pintype "passive"))
      (node (ref "C6") (pin "2") (pinfunction "2_2") (pintype "passive"))
      (node (ref "R15") (pin "2") (pinfunction "2_2") (pintype "passive"))
      (node (ref "R21") (pin "2") (pinfunction "2_2") (pintype "passive"))
      (node (ref "U1") (pin "37") (pinfunction "VC4_37") (pintype "input"))
    )
    (net (code "8") (name "/C5") (class "Default")
      (node (ref "C6") (pin "1") (pinfunction "1_1") (pintype "passive"))
      (node (ref "D17") (pin "2") (pinfunction "A_2") (pintype "passive"))
      (node (ref "R16") (pin "2") (pinfunction "2_2") (pintype "passive"))
      (node (ref "U1") (pin "36") (pinfunction "VC5_36") (pintype "input"))
    )
    (net (code "9") (name "/C5B") (class "Default")
      (node (ref "C7") (pin "1") (pinfunction "1_1") (pintype "passive"))
      (node (ref "R30") (pin "2") (pinfunction "2_2") (pintype "passive"))
      (node (ref "R35") (pin "2") (pinfunction "2_2") (pintype "passive"))
      (node (ref "U1") (pin "35") (pinfunction "VC5B_35") (pintype "input"))
    )
    (net (code "10") (name "/C5X") (class "Default")
      (node (ref "C23") (pin "2") (pinfunction "2_2") (pintype "passive"))
      (node (ref "C24") (pin "2") (pinfunction "2_2") (pintype "passive"))
      (node (ref "C25") (pin "1") (pinfunction "1_1") (pintype "passive"))
      (node (ref "C27") (pin "2") (pinfunction "2_2") (pintype "passive"))
      (node (ref "C7") (pin "2") (pinfunction "2_2") (pintype "passive"))
      (node (ref "C8") (pin "2") (pinfunction "2_2") (pintype "passive"))
      (node (ref "D17") (pin "1") (pinfunction "K_1") (pintype "passive"))
      (node (ref "R47") (pin "1") (pinfunction "1_1") (pintype "passive"))
      (node (ref "R63") (pin "2") (pinfunction "2_2") (pintype "passive"))
      (node (ref "RT2") (pin "2") (pinfunction "2_2") (pintype "passive"))
      (node (ref "U1") (pin "10") (pinfunction "VC5X_10") (pintype "input"))
    )
    (net (code "11") (name "/C6") (class "Default")
      (node (ref "C8") (pin "1") (pinfunction "1_1") (pintype "passive"))
      (node (ref "C9") (pin "2") (pinfunction "2_2") (pintype "passive"))
      (node (ref "R31") (pin "2") (pinfunction "2_2") (pintype "passive"))
      (node (ref "R36") (pin "2") (pinfunction "2_2") (pintype "passive"))
      (node (ref "U1") (pin "34") (pinfunction "VC6_34") (pintype "input"))
    )
    (net (code "12") (name "/C7") (class "Default")
      (node (ref "C10") (pin "2") (pinfunction "2_2") (pintype "passive"))
      (node (ref "C9") (pin "1") (pinfunction "1_1") (pintype "passive"))
      (node (ref "R32") (pin "2") (pinfunction "2_2") (pintype "passive"))
      (node (ref "R37") (pin "2") (pinfunction "2_2") (pintype "passive"))
      (node (ref "U1") (pin "33") (pinfunction "VC7_33") (pintype "input"))
    )
    (net (code "13") (name "/C8") (class "Default")
      (node (ref "C10") (pin "1") (pinfunction "1_1") (pintype "passive"))
      (node (ref "C11") (pin "2") (pinfunction "2_2") (pintype "passive"))
      (node (ref "R33") (pin "2") (pinfunction "2_2") (pintype "passive"))
      (node (ref "R38") (pin "2") (pinfunction "2_2") (pintype "passive"))
      (node (ref "U1") (pin "31") (pinfunction "VC9_31") (pintype "input"))
      (node (ref "U1") (pin "32") (pinfunction "VC8_32") (pintype "input"))
    )
    (net (code "14") (name "/C9") (class "Default")
      (node (ref "C11") (pin "1") (pinfunction "1_1") (pintype "passive"))
      (node (ref "D18") (pin "2") (pinfunction "A_2") (pintype "passive"))
      (node (ref "R34") (pin "2") (pinfunction "2_2") (pintype "passive"))
      (node (ref "U1") (pin "30") (pinfunction "VC10_30") (pintype "input"))
    )
    (net (code "15") (name "/C10") (class "Default")
      (node (ref "C14") (pin "1") (pinfunction "1_1") (pintype "passive"))
      (node (ref "C15") (pin "2") (pinfunction "2_2") (pintype "passive"))
      (node (ref "R51") (pin "2") (pinfunction "2_2") (pintype "passive"))
      (node (ref "R56") (pin "2") (pinfunction "2_2") (pintype "passive"))
      (node (ref "U1") (pin "28") (pinfunction "VC11_28") (pintype "input"))
    )
    (net (code "16") (name "/C10B") (class "Default")
      (node (ref "C12") (pin "1") (pinfunction "1_1") (pintype "passive"))
      (node (ref "R50") (pin "2") (pinfunction "2_2") (pintype "passive"))
      (node (ref "R55") (pin "2") (pinfunction "2_2") (pintype "passive"))
      (node (ref "U1") (pin "29") (pinfunction "VC10B_29") (pintype "input"))
    )
    (net (code "17") (name "/C10X") (class "Default")
      (node (ref "C12") (pin "2") (pinfunction "2_2") (pintype "passive"))
      (node (ref "C14") (pin "2") (pinfunction "2_2") (pintype "passive"))
      (node (ref "C22") (pin "2") (pinfunction "2_2") (pintype "passive"))
      (node (ref "C25") (pin "2") (pinfunction "2_2") (pintype "passive"))
      (node (ref "C26") (pin "1") (pinfunction "1_1") (pintype "passive"))
      (node (ref "C28") (pin "2") (pinfunction "2_2") (pintype "passive"))
      (node (ref "D18") (pin "1") (pinfunction "K_1") (pintype "passive"))
      (node (ref "R64") (pin "2") (pinfunction "2_2") (pintype "passive"))
      (node (ref "RT3") (pin "2") (pinfunction "2_2") (pintype "passive"))
      (node (ref "U1") (pin "15") (pinfunction "VC10X_15") (pintype "input"))
    )
    (net (code "18") (name "/C11") (class "Default")
      (node (ref "C15") (pin "1") (pinfunction "1_1") (pintype "passive"))
      (node (ref "C16") (pin "2") (pinfunction "2_2") (pintype "passive"))
      (node (ref "R52") (pin "2") (pinfunction "2_2") (pintype "passive"))
      (node (ref "R57") (pin "2") (pinfunction "2_2") (pintype "passive"))
      (node (ref "U1") (pin "27") (pinfunction "VC12_27") (pintype "input"))
    )
    (net (code "19") (name "/C12") (class "Default")
      (node (ref "C16") (pin "1") (pinfunction "1_1") (pintype "passive"))
      (node (ref "C17") (pin "2") (pinfunction "2_2") (pintype "passive"))
      (node (ref "R53") (pin "2") (pinfunction "2_2") (pintype "passive"))
      (node (ref "R58") (pin "2") (pinfunction "2_2") (pintype "passive"))
      (node (ref "U1") (pin "25") (pinfunction "VC14_25") (pintype "input"))
      (node (ref "U1") (pin "26") (pinfunction "VC13_26") (pintype "input"))
    )
    (net (code "20") (name "/C13") (class "Default")
      (node (ref "C17") (pin "1") (pinfunction "1_1") (pintype "passive"))
      (node (ref "D20") (pin "2") (pinfunction "A_2") (pintype "passive"))
      (node (ref "R54") (pin "2") (pinfunction "2_2") (pintype "passive"))
      (node (ref "U1") (pin "24") (pinfunction "VC15_24") (pintype "input"))
    )
    (net (code "21") (name "/CAP1") (class "Default")
      (node (ref "C21") (pin "1") (pinfunction "1_1") (pintype "passive"))
      (node (ref "U1") (pin "7") (pinfunction "CAP1_7") (pintype "passive"))
    )
    (net (code "22") (name "/CAP2") (class "Default")
      (node (ref "C23") (pin "1") (pinfunction "1_1") (pintype "passive"))
      (node (ref "U1") (pin "11") (pinfunction "NC_11") (pintype "passive"))
      (node (ref "U1") (pin "12") (pinfunction "NC_12") (pintype "passive"))
      (node (ref "U1") (pin "14") (pinfunction "CAP2_14") (pintype "passive"))
    )
    (net (code "23") (name "/CAP3") (class "Default")
      (node (ref "C22") (pin "1") (pinfunction "1_1") (pintype "passive"))
      (node (ref "U1") (pin "16") (pinfunction "NC_16") (pintype "passive"))
      (node (ref "U1") (pin "17") (pinfunction "NC_17") (pintype "passive"))
      (node (ref "U1") (pin "19") (pinfunction "CAP3_19") (pintype "passive"))
    )
    (net (code "24") (name "/CHG") (class "Default")
      (node (ref "U1") (pin "2") (pinfunction "CHG_2") (pintype "power_in"))
    )
    (net (code "25") (name "/Cell0") (class "Default")
      (node (ref "D1") (pin "1") (pinfunction "K_1") (pintype "passive"))
      (node (ref "D2") (pin "2") (pinfunction "A_2") (pintype "passive"))
      (node (ref "Q1") (pin "2") (pinfunction "S_2") (pintype "passive"))
      (node (ref "R11") (pin "1") (pinfunction "1_1") (pintype "passive"))
    )
    (net (code "26") (name "/Cell1") (class "Default")
      (node (ref "D3") (pin "2") (pinfunction "A_2") (pintype "passive"))
      (node (ref "Q2") (pin "2") (pinfunction "S_2") (pintype "passive"))
      (node (ref "R1") (pin "2") (pinfunction "2_2") (pintype "passive"))
      (node (ref "R12") (pin "1") (pinfunction "1_1") (pintype "passive"))
      (node (ref "R2") (pin "2") (pinfunction "2_2") (pintype "passive"))
    )
    (net (code "27") (name "/Cell2") (class "Default")
      (node (ref "D4") (pin "2") (pinfunction "A_2") (pintype "passive"))
      (node (ref "Q3") (pin "2") (pinfunction "S_2") (pintype "passive"))
      (node (ref "R13") (pin "1") (pinfunction "1_1") (pintype "passive"))
      (node (ref "R3") (pin "2") (pinfunction "2_2") (pintype "passive"))
      (node (ref "R4") (pin "2") (pinfunction "2_2") (pintype "passive"))
    )
    (net (code "28") (name "/Cell3") (class "Default")
      (node (ref "D5") (pin "2") (pinfunction "A_2") (pintype "passive"))
      (node (ref "Q4") (pin "2") (pinfunction "S_2") (pintype "passive"))
      (node (ref "R14") (pin "1") (pinfunction "1_1") (pintype "passive"))
      (node (ref "R5") (pin "2") (pinfunction "2_2") (pintype "passive"))
      (node (ref "R6") (pin "2") (pinfunction "2_2") (pintype "passive"))
    )
    (net (code "29") (name "/Cell4") (class "Default")
      (node (ref "D6") (pin "2") (pinfunction "A_2") (pintype "passive"))
      (node (ref "Q5") (pin "2") (pinfunction "S_2") (pintype "passive"))
      (node (ref "R15") (pin "1") (pinfunction "1_1") (pintype "passive"))
      (node (ref "R7") (pin "2") (pinfunction "2_2") (pintype "passive"))
      (node (ref "R8") (pin "2") (pinfunction "2_2") (pintype "passive"))
    )
    (net (code "30") (name "/Cell5") (class "Default")
      (node (ref "D7") (pin "2") (pinfunction "A_2") (pintype "passive"))
      (node (ref "Q6") (pin "2") (pinfunction "S_2") (pintype "passive"))
      (node (ref "R10") (pin "2") (pinfunction "2_2") (pintype "passive"))
      (node (ref "R16") (pin "1") (pinfunction "1_1") (pintype "passive"))
      (node (ref "R30") (pin "1") (pinfunction "1_1") (pintype "passive"))
      (node (ref "R63") (pin "1") (pinfunction "1_1") (pintype "passive"))
      (node (ref "R9") (pin "2") (pinfunction "2_2") (pintype "passive"))
    )
    (net (code "31") (name "/Cell6") (class "Default")
      (node (ref "D8") (pin "2") (pinfunction "A_2") (pintype "passive"))
      (node (ref "Q7") (pin "2") (pinfunction "S_2") (pintype "passive"))
      (node (ref "R22") (pin "2") (pinfunction "2_2") (pintype "passive"))
      (node (ref "R23") (pin "2") (pinfunction "2_2") (pintype "passive"))
      (node (ref "R31") (pin "1") (pinfunction "1_1") (pintype "passive"))
    )
    (net (code "32") (name "/Cell7") (class "Default")
      (node (ref "D9") (pin "2") (pinfunction "A_2") (pintype "passive"))
      (node (ref "Q8") (pin "2") (pinfunction "S_2") (pintype "passive"))
      (node (ref "R24") (pin "2") (pinfunction "2_2") (pintype "passive"))
      (node (ref "R25") (pin "2") (pinfunction "2_2") (pintype "passive"))
      (node (ref "R32") (pin "1") (pinfunction "1_1") (pintype "passive"))
    )
    (net (code "33") (name "/Cell8") (class "Default")
      (node (ref "D10") (pin "2") (pinfunction "A_2") (pintype "passive"))
      (node (ref "Q9") (pin "2") (pinfunction "S_2") (pintype "passive"))
      (node (ref "R26") (pin "2") (pinfunction "2_2") (pintype "passive"))
      (node (ref "R27") (pin "2") (pinfunction "2_2") (pintype "passive"))
      (node (ref "R33") (pin "1") (pinfunction "1_1") (pintype "passive"))
    )
    (net (code "34") (name "/Cell9") (class "Default")
      (node (ref "D12") (pin "2") (pinfunction "A_2") (pintype "passive"))
      (node (ref "Q10") (pin "2") (pinfunction "S_2") (pintype "passive"))
      (node (ref "R28") (pin "2") (pinfunction "2_2") (pintype "passive"))
      (node (ref "R29") (pin "2") (pinfunction "2_2") (pintype "passive"))
      (node (ref "R34") (pin "1") (pinfunction "1_1") (pintype "passive"))
      (node (ref "R50") (pin "1") (pinfunction "1_1") (pintype "passive"))
      (node (ref "R64") (pin "1") (pinfunction "1_1") (pintype "passive"))
    )
    (net (code "35") (name "/Cell10") (class "Default")
      (node (ref "D13") (pin "2") (pinfunction "A_2") (pintype "passive"))
      (node (ref "Q11") (pin "2") (pinfunction "S_2") (pintype "passive"))
      (node (ref "R39") (pin "2") (pinfunction "2_2") (pintype "passive"))
      (node (ref "R40") (pin "2") (pinfunction "2_2") (pintype "passive"))
      (node (ref "R51") (pin "1") (pinfunction "1_1") (pintype "passive"))
    )
    (net (code "36") (name "/Cell11") (class "Default")
      (node (ref "D14") (pin "2") (pinfunction "A_2") (pintype "passive"))
      (node (ref "Q12") (pin "2") (pinfunction "S_2") (pintype "passive"))
      (node (ref "R41") (pin "2") (pinfunction "2_2") (pintype "passive"))
      (node (ref "R42") (pin "2") (pinfunction "2_2") (pintype "passive"))
      (node (ref "R52") (pin "1") (pinfunction "1_1") (pintype "passive"))
    )
    (net (code "37") (name "/Cell12") (class "Default")
      (node (ref "D15") (pin "2") (pinfunction "A_2") (pintype "passive"))
      (node (ref "Q13") (pin "2") (pinfunction "S_2") (pintype "passive"))
      (node (ref "R43") (pin "2") (pinfunction "2_2") (pintype "passive"))
      (node (ref "R44") (pin "2") (pinfunction "2_2") (pintype "passive"))
      (node (ref "R53") (pin "1") (pinfunction "1_1") (pintype "passive"))
    )
    (net (code "38") (name "/Cell13") (class "Default")
      (node (ref "C18") (pin "2") (pinfunction "2_2") (pintype "passive"))
      (node (ref "R45") (pin "2") (pinfunction "2_2") (pintype "passive"))
      (node (ref "R46") (pin "2") (pinfunction "2_2") (pintype "passive"))
      (node (ref "R48") (pin "1") (pinfunction "1_1") (pintype "passive"))
      (node (ref "R54") (pin "1") (pinfunction "1_1") (pintype "passive"))
      (node (ref "R65") (pin "1") (pinfunction "1_1") (pintype "passive"))
    )
    (net (code "39") (name "/DCHG") (class "Default")
      (node (ref "U1") (pin "1") (pinfunction "DSG_1") (pintype "power_in"))
    )
    (net (code "40") (name "/Pack+") (class "Default")
      (node (ref "D16") (pin "1") (pinfunction "K_1") (pintype "passive"))
      (node (ref "Q15") (pin "2") (pinfunction "S_2") (pintype "passive"))
      (node (ref "R59") (pin "2") (pinfunction "2_2") (pintype "passive"))
    )
    (net (code "41") (name "/Pack-") (class "Default")
      (node (ref "D21") (pin "2") (pinfunction "A_2") (pintype "passive"))
      (node (ref "R66") (pin "1") (pinfunction "1_1") (pintype "passive"))
    )
    (net (code "42") (name "/REGOUT") (class "Default")
      (node (ref "C30") (pin "1") (pinfunction "1_1") (pintype "passive"))
      (node (ref "U1") (pin "8") (pinfunction "REGOUT_8") (pintype "power_in"))
    )
    (net (code "43") (name "/REGSRC") (class "Default")
      (node (ref "C13") (pin "1") (pinfunction "1_1") (pintype "passive"))
      (node (ref "D11") (pin "1") (pinfunction "K_1") (pintype "passive"))
      (node (ref "R49") (pin "2") (pinfunction "2_2") (pintype "passive"))
      (node (ref "U1") (pin "9") (pinfunction "REGSRC_9") (pintype "power_in"))
    )
    (net (code "44") (name "/SCL") (class "Default")
      (node (ref "U1") (pin "5") (pinfunction "SCL_5") (pintype "bidirectional"))
    )
    (net (code "45") (name "/SDA") (class "Default")
      (node (ref "U1") (pin "4") (pinfunction "SDA_4") (pintype "bidirectional"))
    )
    (net (code "46") (name "/SRN_M") (class "Default")
      (node (ref "U1") (pin "43") (pinfunction "SRN_43") (pintype "input"))
    )
    (net (code "47") (name "/SRP_M") (class "Default")
      (node (ref "U1") (pin "42") (pinfunction "SRP_42") (pintype "input"))
    )
    (net (code "48") (name "/TS1") (class "Default")
      (node (ref "C29") (pin "1") (pinfunction "1_1") (pintype "passive"))
      (node (ref "D22") (pin "1") (pinfunction "K_1") (pintype "passive"))
      (node (ref "RT1") (pin "2") (pinfunction "2_2") (pintype "passive"))
      (node (ref "S1") (pin "1") (pinfunction "1_1") (pintype "passive"))
      (node (ref "U1") (pin "6") (pinfunction "TS1_6") (pintype "input"))
    )
    (net (code "49") (name "/Wake") (class "Default")
      (node (ref "R61") (pin "2") (pinfunction "2_2") (pintype "passive"))
    )
    (net (code "50") (name "GND") (class "Default")
      (node (ref "C1") (pin "2") (pinfunction "2_2") (pintype "passive"))
      (node (ref "C13") (pin "2") (pinfunction "2_2") (pintype "passive"))
      (node (ref "C19") (pin "2") (pinfunction "2_2") (pintype "passive"))
      (node (ref "C2") (pin "2") (pinfunction "2_2") (pintype "passive"))
      (node (ref "C21") (pin "2") (pinfunction "2_2") (pintype "passive"))
      (node (ref "C24") (pin "1") (pinfunction "1_1") (pintype "passive"))
      (node (ref "C29") (pin "2") (pinfunction "2_2") (pintype "passive"))
      (node (ref "C30") (pin "2") (pinfunction "2_2") (pintype "passive"))
      (node (ref "D1") (pin "2") (pinfunction "A_2") (pintype "passive"))
      (node (ref "R60") (pin "1") (pinfunction "1_1") (pintype "passive"))
      (node (ref "RT1") (pin "1") (pinfunction "1_1") (pintype "passive"))
      (node (ref "U1") (pin "3") (pinfunction "VSS_3") (pintype "power_in"))
    )
    (net (code "51") (name "Net-(C20-Pad1)") (class "Default")
      (node (ref "C20") (pin "1") (pinfunction "1_1") (pintype "passive"))
      (node (ref "R62") (pin "2") (pinfunction "2_2") (pintype "passive"))
      (node (ref "R67") (pin "2") (pinfunction "2_2") (pintype "passive"))
    )
    (net (code "52") (name "Net-(D2-K)") (class "Default")
      (node (ref "D2") (pin "1") (pinfunction "K_1") (pintype "passive"))
      (node (ref "Q1") (pin "1") (pinfunction "G_1") (pintype "passive"))
      (node (ref "R17") (pin "1") (pinfunction "1_1") (pintype "passive"))
    )
    (net (code "53") (name "Net-(D3-K)") (class "Default")
      (node (ref "D3") (pin "1") (pinfunction "K_1") (pintype "passive"))
      (node (ref "Q2") (pin "1") (pinfunction "G_1") (pintype "passive"))
      (node (ref "R18") (pin "1") (pinfunction "1_1") (pintype "passive"))
    )
    (net (code "54") (name "Net-(D4-K)") (class "Default")
      (node (ref "D4") (pin "1") (pinfunction "K_1") (pintype "passive"))
      (node (ref "Q3") (pin "1") (pinfunction "G_1") (pintype "passive"))
      (node (ref "R19") (pin "1") (pinfunction "1_1") (pintype "passive"))
    )
    (net (code "55") (name "Net-(D5-K)") (class "Default")
      (node (ref "D5") (pin "1") (pinfunction "K_1") (pintype "passive"))
      (node (ref "Q4") (pin "1") (pinfunction "G_1") (pintype "passive"))
      (node (ref "R20") (pin "1") (pinfunction "1_1") (pintype "passive"))
    )
    (net (code "56") (name "Net-(D6-K)") (class "Default")
      (node (ref "D6") (pin "1") (pinfunction "K_1") (pintype "passive"))
      (node (ref "Q5") (pin "1") (pinfunction "G_1") (pintype "passive"))
      (node (ref "R21") (pin "1") (pinfunction "1_1") (pintype "passive"))
    )
    (net (code "57") (name "Net-(D7-K)") (class "Default")
      (node (ref "D7") (pin "1") (pinfunction "K_1") (pintype "passive"))
      (node (ref "Q6") (pin "1") (pinfunction "G_1") (pintype "passive"))
      (node (ref "R35") (pin "1") (pinfunction "1_1") (pintype "passive"))
    )
    (net (code "58") (name "Net-(D8-K)") (class "Default")
      (node (ref "D8") (pin "1") (pinfunction "K_1") (pintype "passive"))
      (node (ref "Q7") (pin "1") (pinfunction "G_1") (pintype "passive"))
      (node (ref "R36") (pin "1") (pinfunction "1_1") (pintype "passive"))
    )
    (net (code "59") (name "Net-(D9-K)") (class "Default")
      (node (ref "D9") (pin "1") (pinfunction "K_1") (pintype "passive"))
      (node (ref "Q8") (pin "1") (pinfunction "G_1") (pintype "passive"))
      (node (ref "R37") (pin "1") (pinfunction "1_1") (pintype "passive"))
    )
    (net (code "60") (name "Net-(D10-K)") (class "Default")
      (node (ref "D10") (pin "1") (pinfunction "K_1") (pintype "passive"))
      (node (ref "Q9") (pin "1") (pinfunction "G_1") (pintype "passive"))
      (node (ref "R38") (pin "1") (pinfunction "1_1") (pintype "passive"))
    )
    (net (code "61") (name "Net-(D11-A)") (class "Default")
      (node (ref "D11") (pin "2") (pinfunction "A_2") (pintype "passive"))
      (node (ref "Q14") (pin "2") (pinfunction "S_2") (pintype "passive"))
      (node (ref "R49") (pin "1") (pinfunction "1_1") (pintype "passive"))
    )
    (net (code "62") (name "Net-(D12-K)") (class "Default")
      (node (ref "D12") (pin "1") (pinfunction "K_1") (pintype "passive"))
      (node (ref "Q10") (pin "1") (pinfunction "G_1") (pintype "passive"))
      (node (ref "R55") (pin "1") (pinfunction "1_1") (pintype "passive"))
    )
    (net (code "63") (name "Net-(D13-K)") (class "Default")
      (node (ref "D13") (pin "1") (pinfunction "K_1") (pintype "passive"))
      (node (ref "Q11") (pin "1") (pinfunction "G_1") (pintype "passive"))
      (node (ref "R56") (pin "1") (pinfunction "1_1") (pintype "passive"))
    )
    (net (code "64") (name "Net-(D14-K)") (class "Default")
      (node (ref "D14") (pin "1") (pinfunction "K_1") (pintype "passive"))
      (node (ref "Q12") (pin "1") (pinfunction "G_1") (pintype "passive"))
      (node (ref "R57") (pin "1") (pinfunction "1_1") (pintype "passive"))
    )
    (net (code "65") (name "Net-(D15-K)") (class "Default")
      (node (ref "D15") (pin "1") (pinfunction "K_1") (pintype "passive"))
      (node (ref "Q13") (pin "1") (pinfunction "G_1") (pintype "passive"))
      (node (ref "R58") (pin "1") (pinfunction "1_1") (pintype "passive"))
    )
    (net (code "66") (name "Net-(D16-A)") (class "Default")
      (node (ref "C18") (pin "1") (pinfunction "1_1") (pintype "passive"))
      (node (ref "D16") (pin "2") (pinfunction "A_2") (pintype "passive"))
      (node (ref "Q15") (pin "1") (pinfunction "G_1") (pintype "passive"))
      (node (ref "R59") (pin "1") (pinfunction "1_1") (pintype "passive"))
    )
    (net (code "67") (name "Net-(D19-A)") (class "Default")
      (node (ref "D19") (pin "2") (pinfunction "A_2") (pintype "passive"))
      (node (ref "R61") (pin "1") (pinfunction "1_1") (pintype "passive"))
    )
    (net (code "68") (name "Net-(D19-K)") (class "Default")
      (node (ref "D19") (pin "1") (pinfunction "K_1") (pintype "passive"))
      (node (ref "D21") (pin "1") (pinfunction "K_1") (pintype "passive"))
      (node (ref "D22") (pin "2") (pinfunction "A_2") (pintype "passive"))
      (node (ref "R66") (pin "2") (pinfunction "2_2") (pintype "passive"))
      (node (ref "R67") (pin "1") (pinfunction "1_1") (pintype "passive"))
    )
    (net (code "69") (name "Net-(Q1-D)") (class "Default")
      (node (ref "Q1") (pin "3") (pinfunction "D_3") (pintype "passive"))
      (node (ref "R1") (pin "1") (pinfunction "1_1") (pintype "passive"))
      (node (ref "R2") (pin "1") (pinfunction "1_1") (pintype "passive"))
    )
    (net (code "70") (name "Net-(Q2-D)") (class "Default")
      (node (ref "Q2") (pin "3") (pinfunction "D_3") (pintype "passive"))
      (node (ref "R3") (pin "1") (pinfunction "1_1") (pintype "passive"))
      (node (ref "R4") (pin "1") (pinfunction "1_1") (pintype "passive"))
    )
    (net (code "71") (name "Net-(Q3-D)") (class "Default")
      (node (ref "Q3") (pin "3") (pinfunction "D_3") (pintype "passive"))
      (node (ref "R5") (pin "1") (pinfunction "1_1") (pintype "passive"))
      (node (ref "R6") (pin "1") (pinfunction "1_1") (pintype "passive"))
    )
    (net (code "72") (name "Net-(Q4-D)") (class "Default")
      (node (ref "Q4") (pin "3") (pinfunction "D_3") (pintype "passive"))
      (node (ref "R7") (pin "1") (pinfunction "1_1") (pintype "passive"))
      (node (ref "R8") (pin "1") (pinfunction "1_1") (pintype "passive"))
    )
    (net (code "73") (name "Net-(Q5-D)") (class "Default")
      (node (ref "Q5") (pin "3") (pinfunction "D_3") (pintype "passive"))
      (node (ref "R10") (pin "1") (pinfunction "1_1") (pintype "passive"))
      (node (ref "R9") (pin "1") (pinfunction "1_1") (pintype "passive"))
    )
    (net (code "74") (name "Net-(Q6-D)") (class "Default")
      (node (ref "Q6") (pin "3") (pinfunction "D_3") (pintype "passive"))
      (node (ref "R22") (pin "1") (pinfunction "1_1") (pintype "passive"))
      (node (ref "R23") (pin "1") (pinfunction "1_1") (pintype "passive"))
    )
    (net (code "75") (name "Net-(Q7-D)") (class "Default")
      (node (ref "Q7") (pin "3") (pinfunction "D_3") (pintype "passive"))
      (node (ref "R24") (pin "1") (pinfunction "1_1") (pintype "passive"))
      (node (ref "R25") (pin "1") (pinfunction "1_1") (pintype "passive"))
    )
    (net (code "76") (name "Net-(Q8-D)") (class "Default")
      (node (ref "Q8") (pin "3") (pinfunction "D_3") (pintype "passive"))
      (node (ref "R26") (pin "1") (pinfunction "1_1") (pintype "passive"))
      (node (ref "R27") (pin "1") (pinfunction "1_1") (pintype "passive"))
    )
    (net (code "77") (name "Net-(Q9-D)") (class "Default")
      (node (ref "Q9") (pin "3") (pinfunction "D_3") (pintype "passive"))
      (node (ref "R28") (pin "1") (pinfunction "1_1") (pintype "passive"))
      (node (ref "R29") (pin "1") (pinfunction "1_1") (pintype "passive"))
    )
    (net (code "78") (name "Net-(Q10-D)") (class "Default")
      (node (ref "Q10") (pin "3") (pinfunction "D_3") (pintype "passive"))
      (node (ref "R39") (pin "1") (pinfunction "1_1") (pintype "passive"))
      (node (ref "R40") (pin "1") (pinfunction "1_1") (pintype "passive"))
    )
    (net (code "79") (name "Net-(Q11-D)") (class "Default")
      (node (ref "Q11") (pin "3") (pinfunction "D_3") (pintype "passive"))
      (node (ref "R41") (pin "1") (pinfunction "1_1") (pintype "passive"))
      (node (ref "R42") (pin "1") (pinfunction "1_1") (pintype "passive"))
    )
    (net (code "80") (name "Net-(Q12-D)") (class "Default")
      (node (ref "Q12") (pin "3") (pinfunction "D_3") (pintype "passive"))
      (node (ref "R43") (pin "1") (pinfunction "1_1") (pintype "passive"))
      (node (ref "R44") (pin "1") (pinfunction "1_1") (pintype "passive"))
    )
    (net (code "81") (name "Net-(Q13-D)") (class "Default")
      (node (ref "Q13") (pin "3") (pinfunction "D_3") (pintype "passive"))
      (node (ref "R45") (pin "1") (pinfunction "1_1") (pintype "passive"))
      (node (ref "R46") (pin "1") (pinfunction "1_1") (pintype "passive"))
    )
    (net (code "82") (name "Net-(Q14-D)") (class "Default")
      (node (ref "Q14") (pin "3") (pinfunction "D_3") (pintype "passive"))
      (node (ref "R48") (pin "2") (pinfunction "2_2") (pintype "passive"))
    )
    (net (code "83") (name "Net-(Q14-G)") (class "Default")
      (node (ref "Q14") (pin "1") (pinfunction "G_1") (pintype "passive"))
      (node (ref "R47") (pin "2") (pinfunction "2_2") (pintype "passive"))
    )
    (net (code "84") (name "Net-(Q15-D)") (class "Default")
      (node (ref "C20") (pin "2") (pinfunction "2_2") (pintype "passive"))
      (node (ref "Q15") (pin "3") (pinfunction "D_3") (pintype "passive"))
      (node (ref "R62") (pin "1") (pinfunction "1_1") (pintype "passive"))
    )
    (net (code "85") (name "Net-(R68-Pad1)") (class "Default")
      (node (ref "R68") (pin "1") (pinfunction "1_1") (pintype "passive"))
      (node (ref "S1") (pin "2") (pinfunction "2_2") (pintype "passive"))
    )
    (net (code "86") (name "Net-(U1-TS2)") (class "Default")
      (node (ref "C27") (pin "1") (pinfunction "1_1") (pintype "passive"))
      (node (ref "RT2") (pin "1") (pinfunction "1_1") (pintype "passive"))
      (node (ref "U1") (pin "13") (pinfunction "TS2_13") (pintype "input"))
    )
    (net (code "87") (name "Net-(U1-TS3)") (class "Default")
      (node (ref "C28") (pin "1") (pinfunction "1_1") (pintype "passive"))
      (node (ref "RT3") (pin "1") (pinfunction "1_1") (pintype "passive"))
      (node (ref "U1") (pin "18") (pinfunction "TS3_18") (pintype "input"))
    )
    (net (code "88") (name "unconnected-(U1-NC-Pad21)") (class "Default")
      (node (ref "U1") (pin "21") (pinfunction "NC_21") (pintype "passive"))
    )
    (net (code "89") (name "unconnected-(U1-NC-Pad22)") (class "Default")
      (node (ref "U1") (pin "22") (pinfunction "NC_22") (pintype "passive"))
    )
    (net (code "90") (name "unconnected-(U1-NC-Pad23)") (class "Default")
      (node (ref "U1") (pin "23") (pinfunction "NC_23") (pintype "passive"))
    )
  )
)
